# sch.net
KiCad netlist of a schematic drawn in Altium Designer
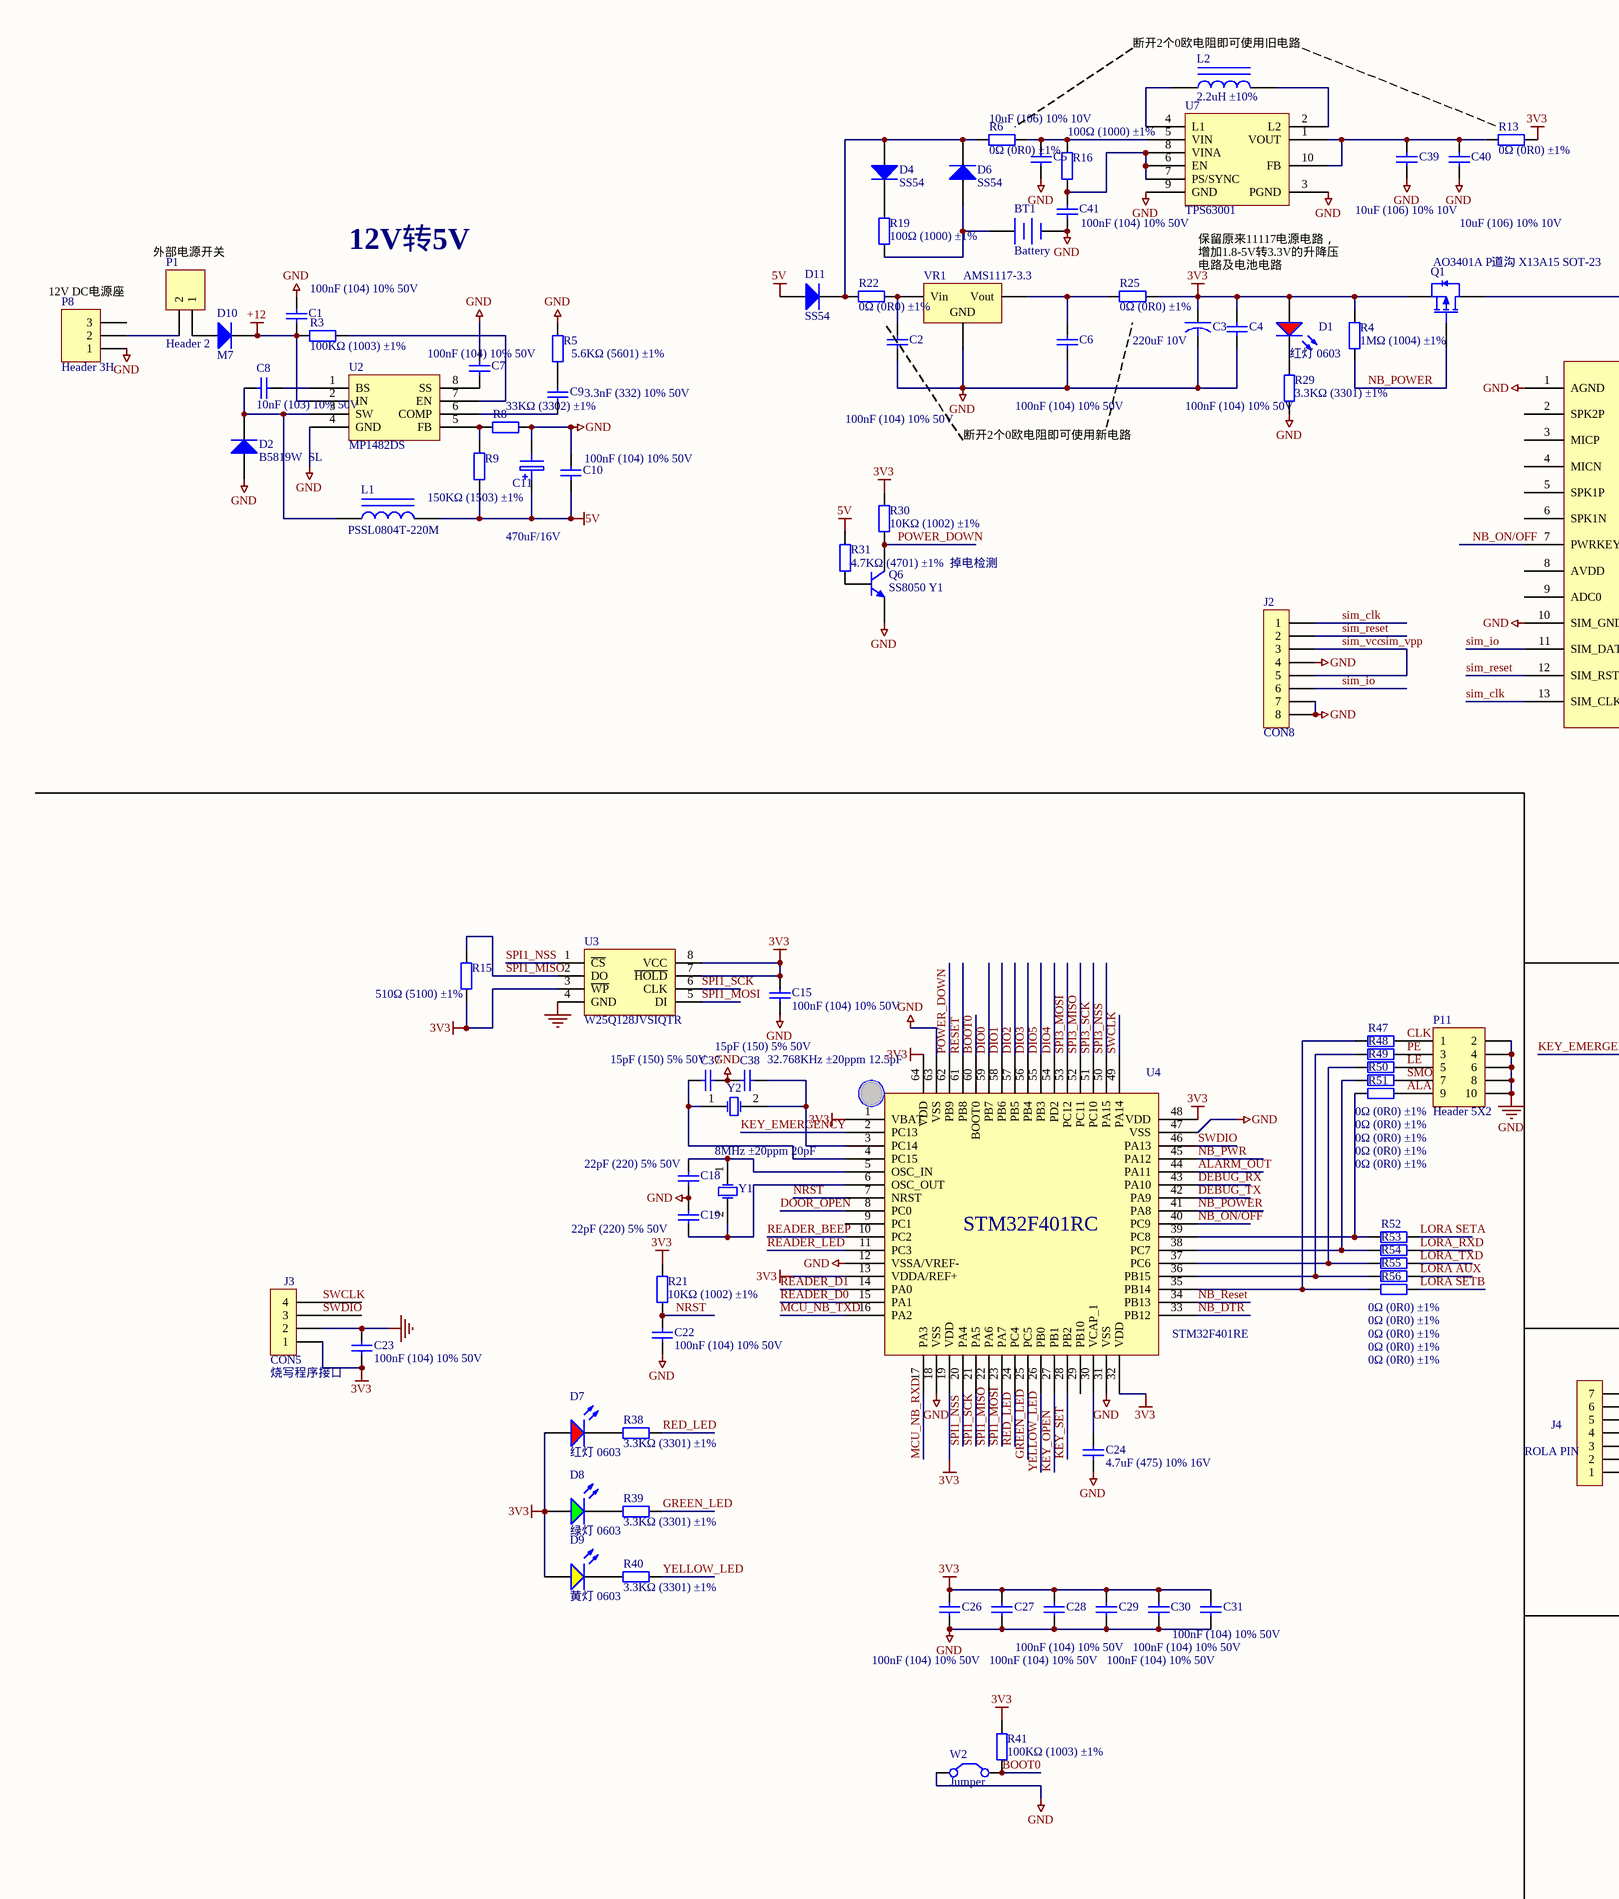
[diagram p0: sch.SchDoc, left]
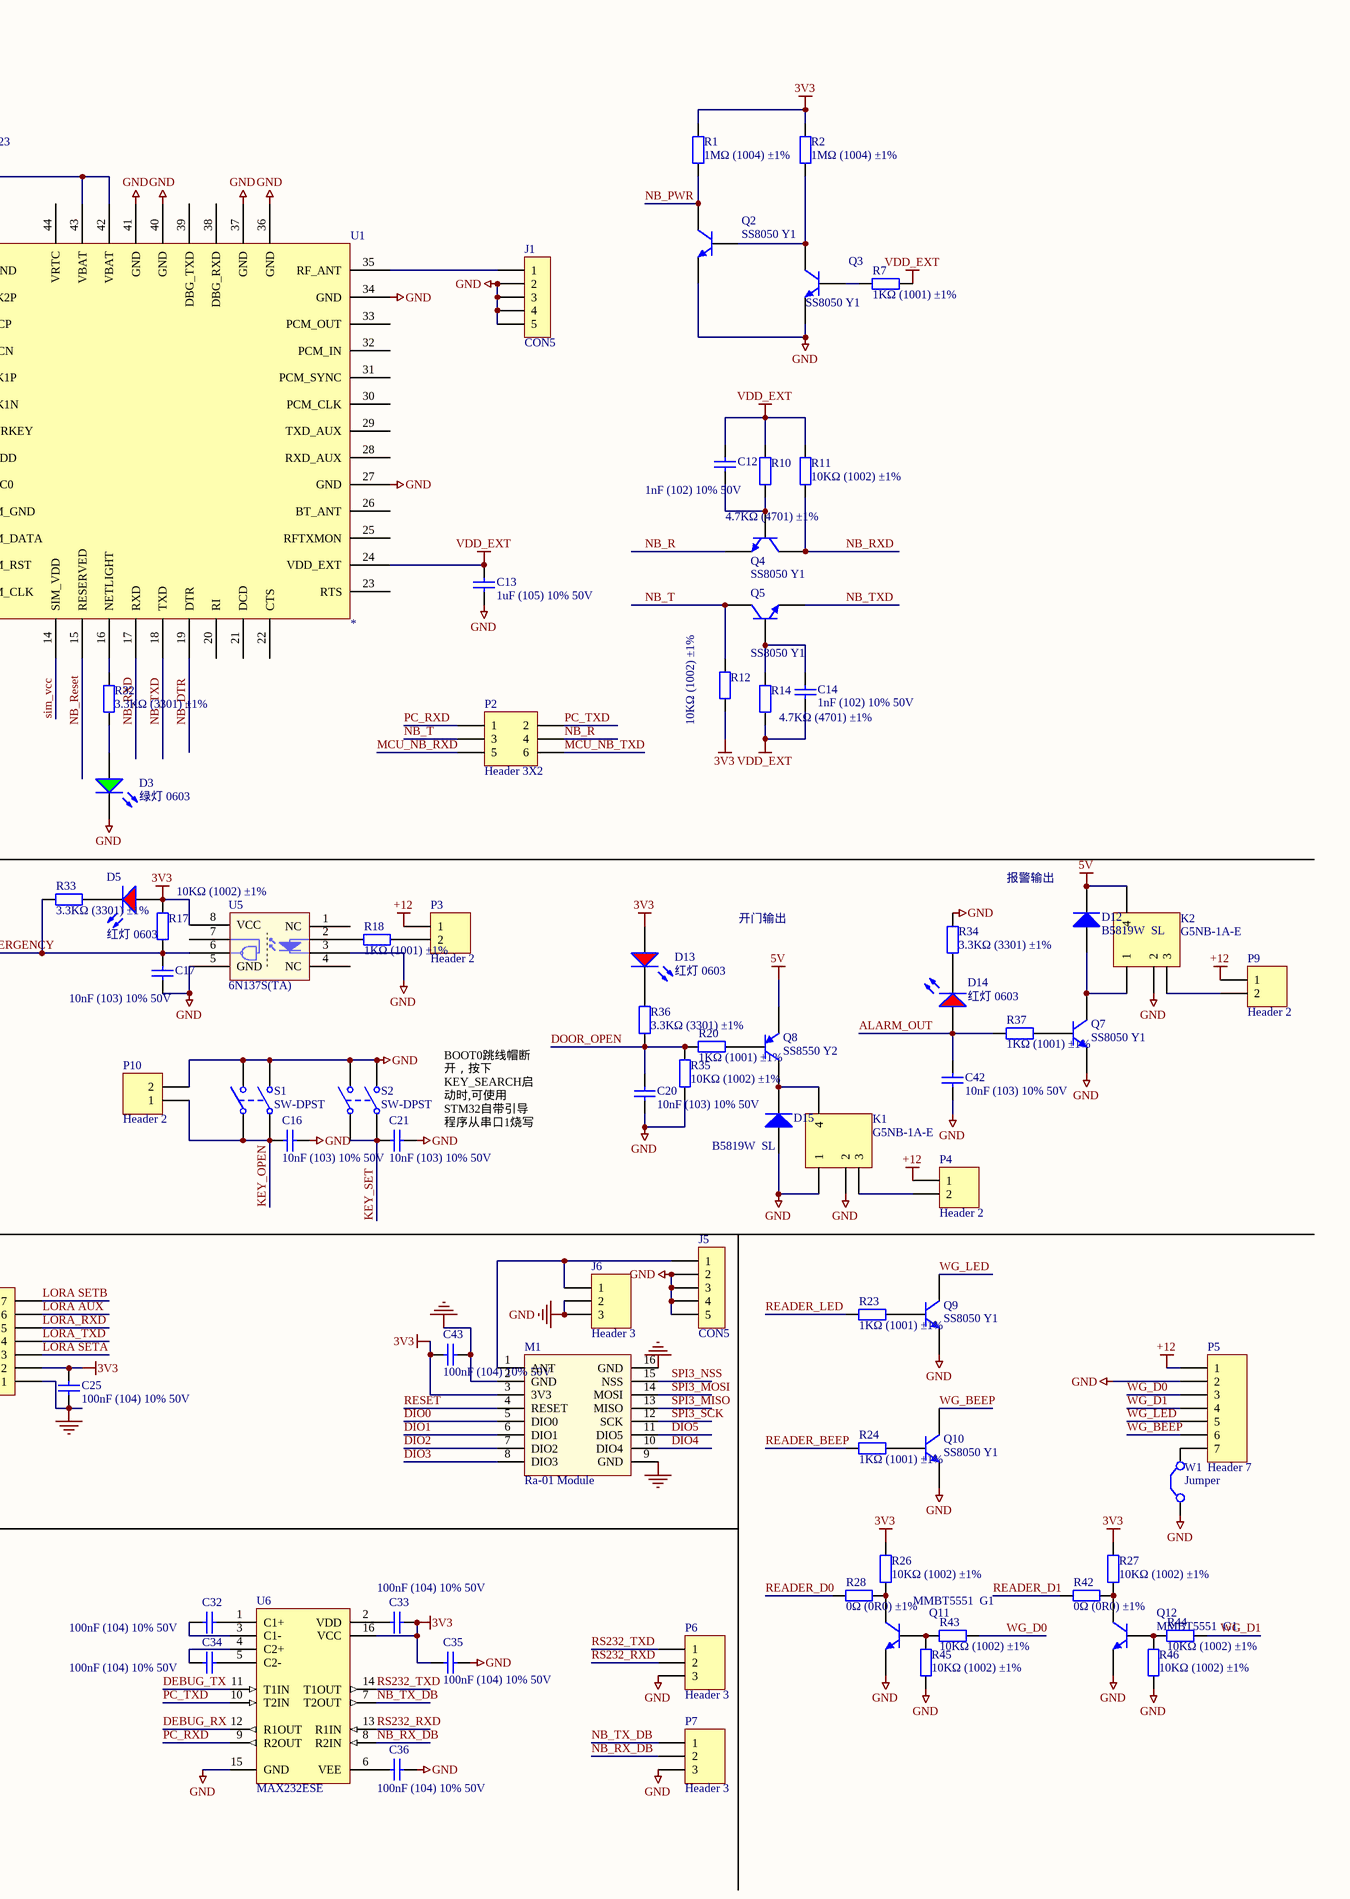
[diagram p1: sch.SchDoc, right]

(export (version "E")
  (design (tool "Eeschema 10.0.6"))
  (components
    (comp (ref "BT1")
      (value "Battery")
      (footprint "3V60R")
      (description "Multicell Battery")
      (fields (field (name "PUBLISHER") "Altium Limited"))
      (libsource (lib "Miscellaneous Devices") (part "Battery"))
    )
    (comp (ref "C1")
      (value "100nF (104) 10% 50V")
      (footprint "0603_C")
      (description "贴片电容")
      (libsource (lib "Cap") (part "0603 100nF (104) 10% 50V"))
    )
    (comp (ref "C2")
      (value "100nF (104) 10% 50V")
      (footprint "0603_C")
      (description "贴片电容")
      (libsource (lib "Cap") (part "0603 100nF (104) 10% 50V"))
    )
    (comp (ref "C3")
      (value "220uF 10V")
      (footprint "153CLV-0807")
      (description "Capacitor")
      (libsource (lib "*") (part "CAPACITOR"))
    )
    (comp (ref "C4")
      (value "100nF (104) 10% 50V")
      (footprint "0603_C")
      (description "贴片电容")
      (libsource (lib "Cap") (part "0603 100nF (104) 10% 50V"))
    )
    (comp (ref "C5")
      (value "10uF (106) 10% 10V")
      (footprint "0603_C")
      (description "贴片电容")
      (libsource (lib "Cap") (part "0603 10uF (106) 10% 10V"))
    )
    (comp (ref "C6")
      (value "100nF (104) 10% 50V")
      (footprint "0603_C")
      (description "贴片电容")
      (libsource (lib "Cap") (part "0603 100nF (104) 10% 50V"))
    )
    (comp (ref "C7")
      (value "100nF (104) 10% 50V")
      (footprint "0603_C")
      (description "贴片电容")
      (libsource (lib "Cap") (part "0603 100nF (104) 10% 50V"))
    )
    (comp (ref "C8")
      (value "10nF (103) 10% 50V")
      (footprint "0603_C")
      (description "贴片电容")
      (libsource (lib "Cap") (part "0603 10nF (103) 10% 50V"))
    )
    (comp (ref "C9")
      (value "3.3nF (332) 10% 50V")
      (footprint "0603_C")
      (description "贴片电容")
      (libsource (lib "Cap") (part "0603 3.3nF (332) 10% 50V"))
    )
    (comp (ref "C10")
      (value "100nF (104) 10% 50V")
      (footprint "0603_C")
      (description "贴片电容")
      (libsource (lib "Cap") (part "0603 100nF (104) 10% 50V"))
    )
    (comp (ref "C11")
      (value "470uF/16V")
      (footprint "153CLV-0810")
      (description "Electrolytic Capacitor")
      (libsource (lib "*") (part "ELECTRO1"))
    )
    (comp (ref "C12")
      (value "1nF (102) 10% 50V")
      (footprint "0603_C")
      (description "贴片电容")
      (libsource (lib "Cap") (part "0603 1nF (102) 10% 50V"))
    )
    (comp (ref "C13")
      (value "1uF (105) 10% 50V")
      (footprint "0603_C")
      (description "贴片电容")
      (libsource (lib "Cap") (part "0603 1uF (105) 10% 50V"))
    )
    (comp (ref "C14")
      (value "1nF (102) 10% 50V")
      (footprint "0603_C")
      (description "贴片电容")
      (libsource (lib "Cap") (part "0603 1nF (102) 10% 50V"))
    )
    (comp (ref "C15")
      (value "100nF (104) 10% 50V")
      (footprint "0603_C")
      (description "贴片电容")
      (libsource (lib "Cap") (part "0603 100nF (104) 10% 50V"))
    )
    (comp (ref "C16")
      (value "10nF (103) 10% 50V")
      (footprint "0603_C")
      (description "贴片电容")
      (libsource (lib "Cap") (part "0603 10nF (103) 10% 50V"))
    )
    (comp (ref "C17")
      (value "10nF (103) 10% 50V")
      (footprint "0603_C")
      (description "贴片电容")
      (libsource (lib "Cap") (part "0603 10nF (103) 10% 50V"))
    )
    (comp (ref "C18")
      (value "22pF (220) 5% 50V")
      (footprint "0603_C")
      (description "贴片电容")
      (libsource (lib "Cap") (part "0603 22pF (220) 5% 50V"))
    )
    (comp (ref "C19")
      (value "22pF (220) 5% 50V")
      (footprint "0603_C")
      (description "贴片电容")
      (libsource (lib "Cap") (part "0603 22pF (220) 5% 50V"))
    )
    (comp (ref "C20")
      (value "10nF (103) 10% 50V")
      (footprint "0603_C")
      (description "贴片电容")
      (libsource (lib "Cap") (part "0603 10nF (103) 10% 50V"))
    )
    (comp (ref "C21")
      (value "10nF (103) 10% 50V")
      (footprint "0603_C")
      (description "贴片电容")
      (libsource (lib "Cap") (part "0603 10nF (103) 10% 50V"))
    )
    (comp (ref "C22")
      (value "100nF (104) 10% 50V")
      (footprint "0603_C")
      (description "贴片电容")
      (libsource (lib "Cap") (part "0603 100nF (104) 10% 50V"))
    )
    (comp (ref "C23")
      (value "100nF (104) 10% 50V")
      (footprint "0603_C")
      (description "贴片电容")
      (libsource (lib "Cap") (part "0603 100nF (104) 10% 50V"))
    )
    (comp (ref "C24")
      (value "4.7uF (475) 10% 16V")
      (footprint "0603_C")
      (description "贴片电容")
      (libsource (lib "Cap") (part "0603 4.7uF (475) 10% 16V"))
    )
    (comp (ref "C25")
      (value "100nF (104) 10% 50V")
      (footprint "0603_C")
      (description "贴片电容")
      (libsource (lib "Cap") (part "0603 100nF (104) 10% 50V"))
    )
    (comp (ref "C26")
      (value "100nF (104) 10% 50V")
      (footprint "0603_C")
      (description "贴片电容")
      (libsource (lib "Cap") (part "0603 100nF (104) 10% 50V"))
    )
    (comp (ref "C27")
      (value "100nF (104) 10% 50V")
      (footprint "0603_C")
      (description "贴片电容")
      (libsource (lib "Cap") (part "0603 100nF (104) 10% 50V"))
    )
    (comp (ref "C28")
      (value "100nF (104) 10% 50V")
      (footprint "0603_C")
      (description "贴片电容")
      (libsource (lib "Cap") (part "0603 100nF (104) 10% 50V"))
    )
    (comp (ref "C29")
      (value "100nF (104) 10% 50V")
      (footprint "0603_C")
      (description "贴片电容")
      (libsource (lib "Cap") (part "0603 100nF (104) 10% 50V"))
    )
    (comp (ref "C30")
      (value "100nF (104) 10% 50V")
      (footprint "0603_C")
      (description "贴片电容")
      (libsource (lib "Cap") (part "0603 100nF (104) 10% 50V"))
    )
    (comp (ref "C31")
      (value "100nF (104) 10% 50V")
      (footprint "0603_C")
      (description "贴片电容")
      (libsource (lib "Cap") (part "0603 100nF (104) 10% 50V"))
    )
    (comp (ref "C32")
      (value "100nF (104) 10% 50V")
      (footprint "0603_C")
      (description "贴片电容")
      (libsource (lib "Cap") (part "0603 100nF (104) 10% 50V"))
    )
    (comp (ref "C33")
      (value "100nF (104) 10% 50V")
      (footprint "0603_C")
      (description "贴片电容")
      (libsource (lib "Cap") (part "0603 100nF (104) 10% 50V"))
    )
    (comp (ref "C34")
      (value "100nF (104) 10% 50V")
      (footprint "0603_C")
      (description "贴片电容")
      (libsource (lib "Cap") (part "0603 100nF (104) 10% 50V"))
    )
    (comp (ref "C35")
      (value "100nF (104) 10% 50V")
      (footprint "0603_C")
      (description "贴片电容")
      (libsource (lib "Cap") (part "0603 100nF (104) 10% 50V"))
    )
    (comp (ref "C36")
      (value "100nF (104) 10% 50V")
      (footprint "0603_C")
      (description "贴片电容")
      (libsource (lib "Cap") (part "0603 100nF (104) 10% 50V"))
    )
    (comp (ref "C37")
      (value "15pF (150) 5% 50V")
      (footprint "0603_C")
      (description "贴片电容")
      (libsource (lib "Cap") (part "0603 15pF (150) 5% 50V"))
    )
    (comp (ref "C38")
      (value "15pF (150) 5% 50V")
      (footprint "0603_C")
      (description "贴片电容")
      (libsource (lib "Cap") (part "0603 15pF (150) 5% 50V"))
    )
    (comp (ref "C39")
      (value "10uF (106) 10% 10V")
      (footprint "0603_C")
      (description "贴片电容")
      (libsource (lib "Cap") (part "0603 10uF (106) 10% 10V"))
    )
    (comp (ref "C40")
      (value "10uF (106) 10% 10V")
      (footprint "0603_C")
      (description "贴片电容")
      (libsource (lib "Cap") (part "0603 10uF (106) 10% 10V"))
    )
    (comp (ref "C41")
      (value "100nF (104) 10% 50V")
      (footprint "0603_C")
      (description "贴片电容")
      (libsource (lib "Cap") (part "0603 100nF (104) 10% 50V"))
    )
    (comp (ref "C42")
      (value "10nF (103) 10% 50V")
      (footprint "0603_C")
      (description "贴片电容")
      (libsource (lib "Cap") (part "0603 10nF (103) 10% 50V"))
    )
    (comp (ref "C43")
      (value "100nF (104) 10% 50V")
      (footprint "0603_C")
      (description "贴片电容")
      (libsource (lib "Cap") (part "0603 100nF (104) 10% 50V"))
    )
    (comp (ref "D1")
      (value "红灯 0603")
      (footprint "0603_LED_S1")
      (description "发光二极管")
      (libsource (lib "LED") (part "0603 红灯"))
    )
    (comp (ref "D2")
      (value "B5819W  SL")
      (footprint "SOD-123")
      (description "肖特基二极管")
      (libsource (lib "Diode") (part "SOD-123 B5819W  SL"))
    )
    (comp (ref "D3")
      (value "绿灯 0603")
      (footprint "0603_LED_S1")
      (description "发光二极管")
      (libsource (lib "LED") (part "0603 绿灯"))
    )
    (comp (ref "D4")
      (value "SS54")
      (footprint "SMA(DO-214AC)_S1")
      (description "二极管")
      (libsource (lib "Diode") (part "SMA(DO-214AC) SS54"))
    )
    (comp (ref "D5")
      (value "红灯 0603")
      (footprint "0603_LED_S1")
      (description "发光二极管")
      (libsource (lib "LED") (part "0603 红灯"))
    )
    (comp (ref "D6")
      (value "SS54")
      (footprint "SMA(DO-214AC)_S1")
      (description "二极管")
      (libsource (lib "Diode") (part "SMA(DO-214AC) SS54"))
    )
    (comp (ref "D7")
      (value "红灯 0603")
      (footprint "0603_LED_S1")
      (description "发光二极管")
      (libsource (lib "LED") (part "0603 红灯"))
    )
    (comp (ref "D8")
      (value "绿灯 0603")
      (footprint "0603_LED_S1")
      (description "发光二极管")
      (libsource (lib "LED") (part "0603 绿灯"))
    )
    (comp (ref "D9")
      (value "黄灯 0603")
      (footprint "0603_LED_S1")
      (description "发光二极管")
      (libsource (lib "LED") (part "0603 黄灯"))
    )
    (comp (ref "D10")
      (value "M7")
      (footprint "SMA(DO-214AC)_S1")
      (description "二极管")
      (libsource (lib "Diode") (part "SMA(DO-214AC) M7"))
    )
    (comp (ref "D11")
      (value "SS54")
      (footprint "SMA(DO-214AC)_S1")
      (description "二极管")
      (libsource (lib "Diode") (part "SMA(DO-214AC) SS54"))
    )
    (comp (ref "D12")
      (value "B5819W  SL")
      (footprint "SOD-123")
      (description "肖特基二极管")
      (libsource (lib "Diode") (part "SOD-123 B5819W  SL"))
    )
    (comp (ref "D13")
      (value "红灯 0603")
      (footprint "0603_LED_S1")
      (description "发光二极管")
      (libsource (lib "LED") (part "0603 红灯"))
    )
    (comp (ref "D14")
      (value "红灯 0603")
      (footprint "0603_LED_S1")
      (description "发光二极管")
      (libsource (lib "LED") (part "0603 红灯"))
    )
    (comp (ref "D15")
      (value "B5819W  SL")
      (footprint "SOD-123")
      (description "肖特基二极管")
      (libsource (lib "Diode") (part "SOD-123 B5819W  SL"))
    )
    (comp (ref "J1")
      (value "CON5")
      (footprint "T-5P")
      (description "Connector")
      (libsource (lib "*") (part "CON5"))
    )
    (comp (ref "J2")
      (value "CON8")
      (footprint "NANOSIM")
      (description "Connector")
      (libsource (lib "*") (part "CON8"))
    )
    (comp (ref "J3")
      (value "CON5")
      (footprint "SIP4")
      (description "Connector")
      (libsource (lib "*") (part "CON4"))
    )
    (comp (ref "J4")
      (value "ROLA PIN")
      (footprint "ROLA MODULE")
      (description "Connector")
      (libsource (lib "*") (part "CON7"))
    )
    (comp (ref "J5")
      (value "CON5")
      (footprint "T-5P")
      (description "Connector")
      (libsource (lib "*") (part "CON5"))
    )
    (comp (ref "J6")
      (value "Header 3")
      (footprint "COAXIAL/SMD/CON/V/I-PEX/W08-5801")
      (description "Header, 3-Pin")
      (fields (field (name "PUBLISHER") "Altium Limited"))
      (libsource (lib "Miscellaneous Connectors") (part "Header 3"))
    )
    (comp (ref "K1") (value "G5NB-1A-E") (footprint "G5NB-1A") (libsource (lib "*") (part "G5NB-1A-E")))
    (comp (ref "K2") (value "G5NB-1A-E") (footprint "G5NB-1A") (libsource (lib "*") (part "G5NB-1A-E")))
    (comp (ref "L1") (value "PSSL0804T-220M") (footprint "L7-8") (libsource (lib "*") (part "INDUCTOR IRON")))
    (comp (ref "L2")
      (value "2.2uH ±10%")
      (footprint "L4532M")
      (description "贴片电感")
      (libsource (lib "IUD") (part "0805 2.2uH 10%"))
    )
    (comp (ref "M1")
      (value "Ra-01 Module")
      (footprint "Ra-01 Module")
      (libsource (lib "Ra-02 Module") (part "Ra-01 Module"))
    )
    (comp (ref "P1")
      (value "Header 2")
      (footprint "MSTBV2")
      (description "Header, 2-Pin")
      (fields (field (name "PUBLISHER") "Altium Limited"))
      (libsource (lib "Miscellaneous Connectors") (part "Header 2"))
    )
    (comp (ref "P2")
      (value "Header 3X2")
      (footprint "HDR2X3")
      (description "Header, 3-Pin, Dual row")
      (fields (field (name "PUBLISHER") "Altium Limited"))
      (libsource (lib "Miscellaneous Connectors") (part "Header 3X2"))
    )
    (comp (ref "P3")
      (value "Header 2")
      (footprint "MSTBV2")
      (description "Header, 2-Pin")
      (fields (field (name "PUBLISHER") "Altium Limited"))
      (libsource (lib "Miscellaneous Connectors") (part "Header 2"))
    )
    (comp (ref "P4")
      (value "Header 2")
      (footprint "MSTBV2")
      (description "Header, 2-Pin")
      (fields (field (name "PUBLISHER") "Altium Limited"))
      (libsource (lib "Miscellaneous Connectors") (part "Header 2"))
    )
    (comp (ref "P5")
      (value "Header 7")
      (footprint "MSTBV7")
      (description "Header, 7-Pin")
      (fields (field (name "PUBLISHER") "Altium Limited"))
      (libsource (lib "Miscellaneous Connectors") (part "Header 7"))
    )
    (comp (ref "P6")
      (value "Header 3")
      (footprint "HDR1X3")
      (description "Header, 3-Pin")
      (fields (field (name "PUBLISHER") "Altium Limited"))
      (libsource (lib "Miscellaneous Connectors") (part "Header 3"))
    )
    (comp (ref "P7")
      (value "Header 3")
      (footprint "HDR1X3")
      (description "Header, 3-Pin")
      (fields (field (name "PUBLISHER") "Altium Limited"))
      (libsource (lib "Miscellaneous Connectors") (part "Header 3"))
    )
    (comp (ref "P8")
      (value "Header 3H")
      (footprint "POWER_SOCK _INSERT_5")
      (description "Header, 3-Pin, Right Angle")
      (fields (field (name "PUBLISHER") "Altium Limited"))
      (libsource (lib "Miscellaneous Connectors") (part "Header 3H"))
    )
    (comp (ref "P9")
      (value "Header 2")
      (footprint "MSTBV2")
      (description "Header, 2-Pin")
      (fields (field (name "PUBLISHER") "Altium Limited"))
      (libsource (lib "Miscellaneous Connectors") (part "Header 2"))
    )
    (comp (ref "P10")
      (value "Header 2")
      (footprint "MSTBV2")
      (description "Header, 2-Pin")
      (fields (field (name "PUBLISHER") "Altium Limited"))
      (libsource (lib "") (part "Header 2_1"))
    )
    (comp (ref "P11")
      (value "Header 5X2")
      (footprint "ML10")
      (description "Header, 5-Pin, Dual row")
      (fields (field (name "PUBLISHER") "Altium Limited"))
      (libsource (lib "Miscellaneous Connectors") (part "Header 5X2"))
    )
    (comp (ref "Q1")
      (value "AO3401A P道沟 X13A15 SOT-23")
      (footprint "SOT-23-3L")
      (description "MOS(场效应管)")
      (libsource (lib "MOS") (part "AO3401A P道沟 X13A15 SOT-23"))
    )
    (comp (ref "Q2")
      (value "SS8050 Y1")
      (footprint "SOT-23(SOT-23-3)")
      (description "三极管")
      (libsource (lib "Transistor_NPN") (part "SOT-23 SS8050 Y1"))
    )
    (comp (ref "Q3")
      (value "SS8050 Y1")
      (footprint "SOT-23(SOT-23-3)")
      (description "三极管")
      (libsource (lib "Transistor_NPN") (part "SOT-23 SS8050 Y1"))
    )
    (comp (ref "Q4")
      (value "SS8050 Y1")
      (footprint "SOT-23(SOT-23-3)")
      (description "三极管")
      (libsource (lib "Transistor_NPN") (part "SOT-23 SS8050 Y1"))
    )
    (comp (ref "Q5")
      (value "SS8050 Y1")
      (footprint "SOT-23(SOT-23-3)")
      (description "三极管")
      (libsource (lib "Transistor_NPN") (part "SOT-23 SS8050 Y1"))
    )
    (comp (ref "Q6")
      (value "SS8050 Y1")
      (footprint "SOT-23(SOT-23-3)")
      (description "三极管")
      (libsource (lib "Transistor_NPN") (part "SOT-23 SS8050 Y1"))
    )
    (comp (ref "Q7")
      (value "SS8050 Y1")
      (footprint "SOT-23(SOT-23-3)")
      (description "三极管")
      (libsource (lib "Transistor_NPN") (part "SOT-23 SS8050 Y1"))
    )
    (comp (ref "Q8")
      (value "SS8550 Y2")
      (footprint "SOT-23(SOT-23-3)")
      (description "三极管")
      (libsource (lib "Transistor_PNP") (part "SOT-23 SS8550 Y2"))
    )
    (comp (ref "Q9")
      (value "SS8050 Y1")
      (footprint "SOT-23(SOT-23-3)")
      (description "三极管")
      (libsource (lib "Transistor_NPN") (part "SOT-23 SS8050 Y1"))
    )
    (comp (ref "Q10")
      (value "SS8050 Y1")
      (footprint "SOT-23(SOT-23-3)")
      (description "三极管")
      (libsource (lib "Transistor_NPN") (part "SOT-23 SS8050 Y1"))
    )
    (comp (ref "Q11")
      (value "MMBT5551  G1")
      (footprint "SOT-23(SOT-23-3)")
      (description "三极管")
      (libsource (lib "Transistor_NPN") (part "SOT-23 MMBT5551  G1"))
    )
    (comp (ref "Q12")
      (value "MMBT5551  G1")
      (footprint "SOT-23(SOT-23-3)")
      (description "三极管")
      (libsource (lib "Transistor_NPN") (part "SOT-23 MMBT5551  G1"))
    )
    (comp (ref "R1")
      (value "1MΩ (1004) ±1%")
      (footprint "0603_R")
      (description "贴片电阻")
      (libsource (lib "RES") (part "0603 1MΩ (1004) 1%"))
    )
    (comp (ref "R2")
      (value "1MΩ (1004) ±1%")
      (footprint "0603_R")
      (description "贴片电阻")
      (libsource (lib "RES") (part "0603 1MΩ (1004) 1%"))
    )
    (comp (ref "R3")
      (value "100KΩ (1003) ±1%")
      (footprint "0603_R")
      (description "贴片电阻")
      (libsource (lib "RES") (part "0603 100KΩ (1003) 1%"))
    )
    (comp (ref "R4")
      (value "1MΩ (1004) ±1%")
      (footprint "0603_R")
      (description "贴片电阻")
      (libsource (lib "RES") (part "0603 1MΩ (1004) 1%"))
    )
    (comp (ref "R5")
      (value "5.6KΩ (5601) ±1%")
      (footprint "0603_R")
      (description "贴片电阻")
      (libsource (lib "RES") (part "0603 5.6KΩ (5601) 1%"))
    )
    (comp (ref "R6")
      (value "0Ω (0R0) ±1%")
      (footprint "0603_R")
      (description "贴片电阻")
      (libsource (lib "RES") (part "0603 0Ω (0R0) 1%"))
    )
    (comp (ref "R7")
      (value "1KΩ (1001) ±1%")
      (footprint "0603_R")
      (description "贴片电阻")
      (libsource (lib "RES") (part "0603 1KΩ (1001) 1%"))
    )
    (comp (ref "R8")
      (value "33KΩ (3302) ±1%")
      (footprint "0603_R")
      (description "贴片电阻")
      (libsource (lib "RES") (part "0603 33KΩ (3302) 1%"))
    )
    (comp (ref "R9")
      (value "150KΩ (1503) ±1%")
      (footprint "0603_R")
      (description "贴片电阻")
      (libsource (lib "RES") (part "0603 150KΩ (1503) 1%"))
    )
    (comp (ref "R10")
      (value "4.7KΩ (4701) ±1%")
      (footprint "0603_R")
      (description "贴片电阻")
      (libsource (lib "RES") (part "0603 4.7KΩ (4701) 1%"))
    )
    (comp (ref "R11")
      (value "10KΩ (1002) ±1%")
      (footprint "0603_R")
      (description "贴片电阻")
      (libsource (lib "") (part "0603 10KΩ (1002) 1%_1"))
    )
    (comp (ref "R12")
      (value "10KΩ (1002) ±1%")
      (footprint "0603_R")
      (description "贴片电阻")
      (libsource (lib "") (part "0603 10KΩ (1002) 1%_1"))
    )
    (comp (ref "R13")
      (value "0Ω (0R0) ±1%")
      (footprint "0603_R")
      (description "贴片电阻")
      (libsource (lib "RES") (part "0603 0Ω (0R0) 1%"))
    )
    (comp (ref "R14")
      (value "4.7KΩ (4701) ±1%")
      (footprint "0603_R")
      (description "贴片电阻")
      (libsource (lib "RES") (part "0603 4.7KΩ (4701) 1%"))
    )
    (comp (ref "R15")
      (value "510Ω (5100) ±1%")
      (footprint "0603_R")
      (description "贴片电阻")
      (libsource (lib "RES") (part "0603 510Ω (5100) 1%"))
    )
    (comp (ref "R16")
      (value "100Ω (1000) ±1%")
      (footprint "0603_R")
      (description "贴片电阻")
      (libsource (lib "RES") (part "0603 100Ω (1000) 1%"))
    )
    (comp (ref "R17")
      (value "10KΩ (1002) ±1%")
      (footprint "0603_R")
      (description "贴片电阻")
      (libsource (lib "RES") (part "0603 10KΩ (1002) 1%"))
    )
    (comp (ref "R18")
      (value "1KΩ (1001) ±1%")
      (footprint "1206_R")
      (description "贴片电阻")
      (libsource (lib "RES") (part "1206 1KΩ (1001) 1%"))
    )
    (comp (ref "R19")
      (value "100Ω (1000) ±1%")
      (footprint "0805_R")
      (description "贴片电阻")
      (libsource (lib "RES") (part "0805 100Ω (1000) 1%"))
    )
    (comp (ref "R20")
      (value "1KΩ (1001) ±1%")
      (footprint "0603_R")
      (description "贴片电阻")
      (libsource (lib "RES") (part "0603 1KΩ (1001) 1%"))
    )
    (comp (ref "R21")
      (value "10KΩ (1002) ±1%")
      (footprint "0603_R")
      (description "贴片电阻")
      (libsource (lib "") (part "0603 10KΩ (1002) 1%_1"))
    )
    (comp (ref "R22")
      (value "0Ω (0R0) ±1%")
      (footprint "0603_R")
      (description "贴片电阻")
      (libsource (lib "RES") (part "0603 0Ω (0R0) 1%"))
    )
    (comp (ref "R23")
      (value "1KΩ (1001) ±1%")
      (footprint "0603_R")
      (description "贴片电阻")
      (libsource (lib "RES") (part "0603 1KΩ (1001) 1%"))
    )
    (comp (ref "R24")
      (value "1KΩ (1001) ±1%")
      (footprint "0603_R")
      (description "贴片电阻")
      (libsource (lib "RES") (part "0603 1KΩ (1001) 1%"))
    )
    (comp (ref "R25")
      (value "0Ω (0R0) ±1%")
      (footprint "0603_R")
      (description "贴片电阻")
      (libsource (lib "RES") (part "0603 0Ω (0R0) 1%"))
    )
    (comp (ref "R26")
      (value "10KΩ (1002) ±1%")
      (footprint "0603_R")
      (description "贴片电阻")
      (libsource (lib "RES") (part "0603 10KΩ (1002) 1%"))
    )
    (comp (ref "R27")
      (value "10KΩ (1002) ±1%")
      (footprint "0603_R")
      (description "贴片电阻")
      (libsource (lib "RES") (part "0603 10KΩ (1002) 1%"))
    )
    (comp (ref "R28")
      (value "0Ω (0R0) ±1%")
      (footprint "0603_R")
      (description "贴片电阻")
      (libsource (lib "RES") (part "0603 0Ω (0R0) 1%"))
    )
    (comp (ref "R29")
      (value "3.3KΩ (3301) ±1%")
      (footprint "0603_R")
      (description "贴片电阻")
      (libsource (lib "RES") (part "0603 3.3KΩ (3301) 1%"))
    )
    (comp (ref "R30")
      (value "10KΩ (1002) ±1%")
      (footprint "0603_R")
      (description "贴片电阻")
      (libsource (lib "") (part "0603 10KΩ (1002) 1%_1"))
    )
    (comp (ref "R31")
      (value "4.7KΩ (4701) ±1%")
      (footprint "0603_R")
      (description "贴片电阻")
      (libsource (lib "RES") (part "0603 4.7KΩ (4701) 1%"))
    )
    (comp (ref "R32")
      (value "3.3KΩ (3301) ±1%")
      (footprint "0603_R")
      (description "贴片电阻")
      (libsource (lib "RES") (part "0603 3.3KΩ (3301) 1%"))
    )
    (comp (ref "R33")
      (value "3.3KΩ (3301) ±1%")
      (footprint "0603_R")
      (description "贴片电阻")
      (libsource (lib "") (part "0603 3.3KΩ (3301) 1%_1"))
    )
    (comp (ref "R34")
      (value "3.3KΩ (3301) ±1%")
      (footprint "0603_R")
      (description "贴片电阻")
      (libsource (lib "RES") (part "0603 3.3KΩ (3301) 1%"))
    )
    (comp (ref "R35")
      (value "10KΩ (1002) ±1%")
      (footprint "0603_R")
      (description "贴片电阻")
      (libsource (lib "") (part "0603 10KΩ (1002) 1%_1"))
    )
    (comp (ref "R36")
      (value "3.3KΩ (3301) ±1%")
      (footprint "0603_R")
      (description "贴片电阻")
      (libsource (lib "") (part "0603 3.3KΩ (3301) 1%_2"))
    )
    (comp (ref "R37")
      (value "1KΩ (1001) ±1%")
      (footprint "0603_R")
      (description "贴片电阻")
      (libsource (lib "RES") (part "0603 1KΩ (1001) 1%"))
    )
    (comp (ref "R38")
      (value "3.3KΩ (3301) ±1%")
      (footprint "0603_R")
      (description "贴片电阻")
      (libsource (lib "") (part "0603 3.3KΩ (3301) 1%_1"))
    )
    (comp (ref "R39")
      (value "3.3KΩ (3301) ±1%")
      (footprint "0603_R")
      (description "贴片电阻")
      (libsource (lib "") (part "0603 3.3KΩ (3301) 1%_1"))
    )
    (comp (ref "R40")
      (value "3.3KΩ (3301) ±1%")
      (footprint "0603_R")
      (description "贴片电阻")
      (libsource (lib "") (part "0603 3.3KΩ (3301) 1%_1"))
    )
    (comp (ref "R41")
      (value "100KΩ (1003) ±1%")
      (footprint "0603_R")
      (description "贴片电阻")
      (libsource (lib "") (part "0603 100KΩ (1003) 1%_1"))
    )
    (comp (ref "R42")
      (value "0Ω (0R0) ±1%")
      (footprint "0603_R")
      (description "贴片电阻")
      (libsource (lib "RES") (part "0603 0Ω (0R0) 1%"))
    )
    (comp (ref "R43")
      (value "10KΩ (1002) ±1%")
      (footprint "0603_R")
      (description "贴片电阻")
      (libsource (lib "") (part "0603 10KΩ (1002) 1%_2"))
    )
    (comp (ref "R44")
      (value "10KΩ (1002) ±1%")
      (footprint "0603_R")
      (description "贴片电阻")
      (libsource (lib "") (part "0603 10KΩ (1002) 1%_2"))
    )
    (comp (ref "R45")
      (value "10KΩ (1002) ±1%")
      (footprint "0603_R")
      (description "贴片电阻")
      (libsource (lib "RES") (part "0603 10KΩ (1002) 1%"))
    )
    (comp (ref "R46")
      (value "10KΩ (1002) ±1%")
      (footprint "0603_R")
      (description "贴片电阻")
      (libsource (lib "RES") (part "0603 10KΩ (1002) 1%"))
    )
    (comp (ref "R47")
      (value "0Ω (0R0) ±1%")
      (footprint "0603_R")
      (description "贴片电阻")
      (libsource (lib "RES") (part "0603 0Ω (0R0) 1%"))
    )
    (comp (ref "R48")
      (value "0Ω (0R0) ±1%")
      (footprint "0603_R")
      (description "贴片电阻")
      (libsource (lib "RES") (part "0603 0Ω (0R0) 1%"))
    )
    (comp (ref "R49")
      (value "0Ω (0R0) ±1%")
      (footprint "0603_R")
      (description "贴片电阻")
      (libsource (lib "RES") (part "0603 0Ω (0R0) 1%"))
    )
    (comp (ref "R50")
      (value "0Ω (0R0) ±1%")
      (footprint "0603_R")
      (description "贴片电阻")
      (libsource (lib "RES") (part "0603 0Ω (0R0) 1%"))
    )
    (comp (ref "R51")
      (value "0Ω (0R0) ±1%")
      (footprint "0603_R")
      (description "贴片电阻")
      (libsource (lib "RES") (part "0603 0Ω (0R0) 1%"))
    )
    (comp (ref "R52")
      (value "0Ω (0R0) ±1%")
      (footprint "0603_R")
      (description "贴片电阻")
      (libsource (lib "RES") (part "0603 0Ω (0R0) 1%"))
    )
    (comp (ref "R53")
      (value "0Ω (0R0) ±1%")
      (footprint "0603_R")
      (description "贴片电阻")
      (libsource (lib "RES") (part "0603 0Ω (0R0) 1%"))
    )
    (comp (ref "R54")
      (value "0Ω (0R0) ±1%")
      (footprint "0603_R")
      (description "贴片电阻")
      (libsource (lib "RES") (part "0603 0Ω (0R0) 1%"))
    )
    (comp (ref "R55")
      (value "0Ω (0R0) ±1%")
      (footprint "0603_R")
      (description "贴片电阻")
      (libsource (lib "RES") (part "0603 0Ω (0R0) 1%"))
    )
    (comp (ref "R56")
      (value "0Ω (0R0) ±1%")
      (footprint "0603_R")
      (description "贴片电阻")
      (libsource (lib "RES") (part "0603 0Ω (0R0) 1%"))
    )
    (comp (ref "S1")
      (value "SW-DPST")
      (footprint "12*12_key")
      (description "Double-Pole, Single-Throw Switch")
      (fields (field (name "PUBLISHER") "Altium Limited"))
      (libsource (lib "Miscellaneous Devices") (part "SW-DPST"))
    )
    (comp (ref "S2")
      (value "SW-DPST")
      (footprint "12*12_key")
      (description "Double-Pole, Single-Throw Switch")
      (fields (field (name "PUBLISHER") "Altium Limited"))
      (libsource (lib "Miscellaneous Devices") (part "SW-DPST"))
    )
    (comp (ref "U1") (value "*") (footprint "M26") (libsource (lib "*") (part "M26")))
    (comp (ref "U2")
      (value "MP1482DS")
      (footprint "SOIC-8_150mil")
      (description "电源芯片")
      (libsource (lib "IC") (part "MP1482DS_[C14867]"))
    )
    (comp (ref "U3")
      (value "W25Q128JVSIQTR")
      (footprint "SOIC-8_208mil")
      (description "Flash ROM")
      (libsource (lib "IC") (part "W25Q128JVSIQTR_[C97521]"))
    )
    (comp (ref "U4") (value "STM32F401RE") (footprint "LQFP64") (libsource (lib "*") (part "STM32F401RC")))
    (comp (ref "U5")
      (value "6N137S(TA)")
      (footprint "SMD-8_6.3mm")
      (description "贴片光耦")
      (libsource (lib "IC") (part "6N137S(TA)_[C16496]"))
    )
    (comp (ref "U6")
      (value "MAX232ESE")
      (footprint "SOIC-16_150mil")
      (description "RS232")
      (libsource (lib "IC") (part "MAX232ESE_[C26860]"))
    )
    (comp (ref "U7")
      (value "TPS63001")
      (footprint "DRC-S-PVSON-N10")
      (libsource (lib "Schlib1") (part "TPS63001"))
    )
    (comp (ref "VR1")
      (value "AMS1117-3.3")
      (footprint "SOT-223")
      (description "低压差线性稳压(LDO)")
      (libsource (lib "LDO") (part "SOT-223 AMS1117-3.3"))
    )
    (comp (ref "W1")
      (value "Jumper")
      (footprint "JP1")
      (description "Jumper Wire")
      (fields (field (name "PUBLISHER") "Altium Limited"))
      (libsource (lib "Miscellaneous Devices") (part "Jumper"))
    )
    (comp (ref "W2")
      (value "Jumper")
      (footprint "JP1")
      (description "Jumper Wire")
      (fields (field (name "PUBLISHER") "Altium Limited"))
      (libsource (lib "Miscellaneous Devices") (part "Jumper"))
    )
    (comp (ref "Y1")
      (value "8MHz ±20ppm 20pF")
      (footprint "SMD-5032_2P")
      (description "贴片晶振")
      (libsource (lib "CrystalOscillator") (part "SMD-5032_2P 8MHz 20ppm 20pF"))
    )
    (comp (ref "Y2")
      (value "32.768KHz ±20ppm 12.5pF")
      (footprint "SMD-3215_2P FC - 135")
      (description "贴片晶振")
      (libsource (lib "CrystalOscillator") (part "SMD-3215_2P 32.768KHz 20ppm 12.5pF"))
    )
  )
  (nets
    (net (code "1") (name "+12") (class "Default")
      (node (ref "C1") (pin "2") (pinfunction "2_2") (pintype "passive"))
      (node (ref "D10") (pin "2") (pinfunction "K_2") (pintype "passive"))
      (node (ref "P3") (pin "1") (pinfunction "1_1") (pintype "passive"))
      (node (ref "P4") (pin "1") (pinfunction "1_1") (pintype "passive"))
      (node (ref "P5") (pin "1") (pinfunction "1_1") (pintype "passive"))
      (node (ref "P9") (pin "1") (pinfunction "1_1") (pintype "passive"))
      (node (ref "R3") (pin "1") (pinfunction "1_1") (pintype "passive"))
      (node (ref "U2") (pin "2") (pinfunction "IN_2") (pintype "passive"))
    )
    (net (code "3") (name "/ALARM") (class "Default")
      (node (ref "P11") (pin "9") (pinfunction "9_9") (pintype "passive"))
      (node (ref "R51") (pin "2") (pinfunction "2_2") (pintype "passive"))
    )
    (net (code "4") (name "/ALARM_OUT") (class "Default")
      (node (ref "C42") (pin "1") (pinfunction "1_1") (pintype "passive"))
      (node (ref "D14") (pin "A") (pinfunction "A_A") (pintype "passive"))
      (node (ref "R37") (pin "1") (pinfunction "1_1") (pintype "passive"))
      (node (ref "U4") (pin "44") (pinfunction "PA11_44") (pintype "passive"))
    )
    (net (code "5") (name "/BOOT0") (class "Default")
      (node (ref "R41") (pin "1") (pinfunction "1_1") (pintype "passive"))
      (node (ref "U4") (pin "60") (pinfunction "BOOT0_60") (pintype "passive"))
      (node (ref "W2") (pin "2") (pinfunction "C2_2") (pintype "passive"))
    )
    (net (code "6") (name "/CLK") (class "Default")
      (node (ref "P11") (pin "1") (pinfunction "1_1") (pintype "passive"))
      (node (ref "R47") (pin "2") (pinfunction "2_2") (pintype "passive"))
    )
    (net (code "7") (name "/DEBUG_RX") (class "Default")
      (node (ref "U4") (pin "43") (pinfunction "PA10_43") (pintype "passive"))
      (node (ref "U6") (pin "12") (pinfunction "R1OUT_12") (pintype "output"))
    )
    (net (code "8") (name "/DEBUG_TX") (class "Default")
      (node (ref "U4") (pin "42") (pinfunction "PA9_42") (pintype "passive"))
      (node (ref "U6") (pin "11") (pinfunction "T1IN_11") (pintype "input"))
    )
    (net (code "9") (name "/DIO0") (class "Default")
      (node (ref "M1") (pin "5") (pinfunction "DIO0_5") (pintype "passive"))
      (node (ref "U4") (pin "59") (pinfunction "PB7_59") (pintype "passive"))
    )
    (net (code "10") (name "/DIO1") (class "Default")
      (node (ref "M1") (pin "6") (pinfunction "DIO1_6") (pintype "passive"))
      (node (ref "U4") (pin "58") (pinfunction "PB6_58") (pintype "passive"))
    )
    (net (code "11") (name "/DIO2") (class "Default")
      (node (ref "M1") (pin "7") (pinfunction "DIO2_7") (pintype "passive"))
      (node (ref "U4") (pin "57") (pinfunction "PB5_57") (pintype "passive"))
    )
    (net (code "12") (name "/DIO3") (class "Default")
      (node (ref "M1") (pin "8") (pinfunction "DIO3_8") (pintype "passive"))
      (node (ref "U4") (pin "56") (pinfunction "PB4_56") (pintype "passive"))
    )
    (net (code "13") (name "/DIO4") (class "Default")
      (node (ref "M1") (pin "10") (pinfunction "DIO4_10") (pintype "passive"))
      (node (ref "U4") (pin "54") (pinfunction "PD2_54") (pintype "passive"))
    )
    (net (code "14") (name "/DIO5") (class "Default")
      (node (ref "M1") (pin "11") (pinfunction "DIO5_11") (pintype "passive"))
      (node (ref "U4") (pin "55") (pinfunction "PB3_55") (pintype "passive"))
    )
    (net (code "15") (name "/DOOR_OPEN") (class "Default")
      (node (ref "C20") (pin "1") (pinfunction "1_1") (pintype "passive"))
      (node (ref "R20") (pin "1") (pinfunction "1_1") (pintype "passive"))
      (node (ref "R35") (pin "2") (pinfunction "2_2") (pintype "passive"))
      (node (ref "R36") (pin "1") (pinfunction "1_1") (pintype "passive"))
      (node (ref "U4") (pin "8") (pinfunction "PC0_8") (pintype "passive"))
    )
    (net (code "16") (name "/GREEN_LED") (class "Default")
      (node (ref "R39") (pin "2") (pinfunction "2_2") (pintype "passive"))
      (node (ref "U4") (pin "25") (pinfunction "PC5_25") (pintype "passive"))
    )
    (net (code "17") (name "/KEY_EMERGENCY") (class "Default")
      (node (ref "C17") (pin "2") (pinfunction "2_2") (pintype "passive"))
      (node (ref "R17") (pin "2") (pinfunction "2_2") (pintype "passive"))
      (node (ref "R33") (pin "1") (pinfunction "1_1") (pintype "passive"))
      (node (ref "U4") (pin "2") (pinfunction "PC13_2") (pintype "passive"))
      (node (ref "U5") (pin "6") (pinfunction "VO_6") (pintype "passive"))
    )
    (net (code "18") (name "/KEY_OPEN") (class "Default")
      (node (ref "C16") (pin "1") (pinfunction "1_1") (pintype "passive"))
      (node (ref "P10") (pin "1") (pinfunction "1_1") (pintype "passive"))
      (node (ref "S1") (pin "1") (pinfunction "COMMON1_1") (pintype "passive"))
      (node (ref "S1") (pin "3") (pinfunction "COMMON2_3") (pintype "passive"))
      (node (ref "U4") (pin "27") (pinfunction "PB1_27") (pintype "passive"))
    )
    (net (code "19") (name "/KEY_SET") (class "Default")
      (node (ref "C21") (pin "1") (pinfunction "1_1") (pintype "passive"))
      (node (ref "S2") (pin "1") (pinfunction "COMMON1_1") (pintype "passive"))
      (node (ref "S2") (pin "3") (pinfunction "COMMON2_3") (pintype "passive"))
      (node (ref "U4") (pin "28") (pinfunction "PB2_28") (pintype "passive"))
    )
    (net (code "20") (name "/LE") (class "Default")
      (node (ref "P11") (pin "5") (pinfunction "5_5") (pintype "passive"))
      (node (ref "R49") (pin "2") (pinfunction "2_2") (pintype "passive"))
    )
    (net (code "21") (name "/LORA AUX") (class "Default")
      (node (ref "J4") (pin "6") (pinfunction "6_6") (pintype "passive"))
      (node (ref "R55") (pin "2") (pinfunction "2_2") (pintype "passive"))
    )
    (net (code "22") (name "/LORA SETA") (class "Default")
      (node (ref "J4") (pin "3") (pinfunction "3_3") (pintype "passive"))
      (node (ref "R52") (pin "2") (pinfunction "2_2") (pintype "passive"))
    )
    (net (code "23") (name "/LORA SETB") (class "Default")
      (node (ref "J4") (pin "7") (pinfunction "7_7") (pintype "passive"))
      (node (ref "R56") (pin "2") (pinfunction "2_2") (pintype "passive"))
    )
    (net (code "24") (name "/LORA_RXD") (class "Default")
      (node (ref "J4") (pin "5") (pinfunction "5_5") (pintype "passive"))
      (node (ref "R53") (pin "2") (pinfunction "2_2") (pintype "passive"))
    )
    (net (code "25") (name "/LORA_TXD") (class "Default")
      (node (ref "J4") (pin "4") (pinfunction "4_4") (pintype "passive"))
      (node (ref "R54") (pin "2") (pinfunction "2_2") (pintype "passive"))
    )
    (net (code "26") (name "/MCU_NB_RXD") (class "Default")
      (node (ref "P2") (pin "5") (pinfunction "5_5") (pintype "passive"))
      (node (ref "U4") (pin "17") (pinfunction "PA3_17") (pintype "passive"))
    )
    (net (code "27") (name "/MCU_NB_TXD") (class "Default")
      (node (ref "P2") (pin "6") (pinfunction "6_6") (pintype "passive"))
      (node (ref "U4") (pin "16") (pinfunction "PA2_16") (pintype "passive"))
    )
    (net (code "28") (name "/NB_DTR") (class "Default")
      (node (ref "U1") (pin "19") (pinfunction "DTR_19") (pintype "passive"))
      (node (ref "U4") (pin "33") (pinfunction "PB12_33") (pintype "passive"))
    )
    (net (code "29") (name "/NB_ON{slash}OFF") (class "Default")
      (node (ref "U1") (pin "7") (pinfunction "PWRKEY_7") (pintype "passive"))
      (node (ref "U4") (pin "40") (pinfunction "PC9_40") (pintype "passive"))
    )
    (net (code "30") (name "/NB_POWER") (class "Default")
      (node (ref "Q1") (pin "1") (pinfunction "G_1") (pintype "passive"))
      (node (ref "R4") (pin "1") (pinfunction "1_1") (pintype "passive"))
      (node (ref "U4") (pin "41") (pinfunction "PA8_41") (pintype "passive"))
    )
    (net (code "31") (name "/NB_PWR") (class "Default")
      (node (ref "Q2") (pin "3") (pinfunction "C_3") (pintype "passive"))
      (node (ref "R1") (pin "1") (pinfunction "1_1") (pintype "passive"))
      (node (ref "U4") (pin "45") (pinfunction "PA12_45") (pintype "passive"))
    )
    (net (code "32") (name "/NB_R") (class "Default")
      (node (ref "P2") (pin "4") (pinfunction "4_4") (pintype "passive"))
      (node (ref "Q4") (pin "2") (pinfunction "E_2") (pintype "passive"))
    )
    (net (code "33") (name "/NB_RXD") (class "Default")
      (node (ref "Q4") (pin "3") (pinfunction "C_3") (pintype "passive"))
      (node (ref "R11") (pin "1") (pinfunction "1_1") (pintype "passive"))
      (node (ref "U1") (pin "17") (pinfunction "RXD_17") (pintype "passive"))
    )
    (net (code "34") (name "/NB_RX_DB") (class "Default")
      (node (ref "P7") (pin "2") (pinfunction "2_2") (pintype "passive"))
      (node (ref "U6") (pin "8") (pinfunction "R2IN_8") (pintype "input"))
    )
    (net (code "35") (name "/NB_Reset") (class "Default")
      (node (ref "U1") (pin "15") (pinfunction "RESERVED_15") (pintype "passive"))
      (node (ref "U4") (pin "34") (pinfunction "PB13_34") (pintype "passive"))
    )
    (net (code "36") (name "/NB_T") (class "Default")
      (node (ref "P2") (pin "3") (pinfunction "3_3") (pintype "passive"))
      (node (ref "Q5") (pin "3") (pinfunction "C_3") (pintype "passive"))
      (node (ref "R12") (pin "2") (pinfunction "2_2") (pintype "passive"))
    )
    (net (code "37") (name "/NB_TXD") (class "Default")
      (node (ref "Q5") (pin "2") (pinfunction "E_2") (pintype "passive"))
      (node (ref "U1") (pin "18") (pinfunction "TXD_18") (pintype "passive"))
    )
    (net (code "38") (name "/NB_TX_DB") (class "Default")
      (node (ref "P7") (pin "1") (pinfunction "1_1") (pintype "passive"))
      (node (ref "U6") (pin "7") (pinfunction "T2OUT_7") (pintype "output"))
    )
    (net (code "39") (name "/NRST") (class "Default")
      (node (ref "C22") (pin "1") (pinfunction "1_1") (pintype "passive"))
      (node (ref "R21") (pin "1") (pinfunction "1_1") (pintype "passive"))
      (node (ref "U4") (pin "7") (pinfunction "NRST_7") (pintype "passive"))
    )
    (net (code "40") (name "/PC_RXD") (class "Default")
      (node (ref "P2") (pin "1") (pinfunction "1_1") (pintype "passive"))
      (node (ref "U6") (pin "9") (pinfunction "R2OUT_9") (pintype "output"))
    )
    (net (code "41") (name "/PC_TXD") (class "Default")
      (node (ref "P2") (pin "2") (pinfunction "2_2") (pintype "passive"))
      (node (ref "U6") (pin "10") (pinfunction "T2IN_10") (pintype "input"))
    )
    (net (code "42") (name "/PE") (class "Default")
      (node (ref "P11") (pin "3") (pinfunction "3_3") (pintype "passive"))
      (node (ref "R48") (pin "2") (pinfunction "2_2") (pintype "passive"))
    )
    (net (code "43") (name "/POWER_DOWN") (class "Default")
      (node (ref "Q6") (pin "3") (pinfunction "C_3") (pintype "passive"))
      (node (ref "R30") (pin "1") (pinfunction "1_1") (pintype "passive"))
      (node (ref "U4") (pin "62") (pinfunction "PB9_62") (pintype "passive"))
    )
    (net (code "44") (name "/READER_BEEP") (class "Default")
      (node (ref "R24") (pin "1") (pinfunction "1_1") (pintype "passive"))
      (node (ref "U4") (pin "10") (pinfunction "PC2_10") (pintype "passive"))
    )
    (net (code "45") (name "/READER_D0") (class "Default")
      (node (ref "R28") (pin "1") (pinfunction "1_1") (pintype "passive"))
      (node (ref "U4") (pin "15") (pinfunction "PA1_15") (pintype "passive"))
    )
    (net (code "46") (name "/READER_D1") (class "Default")
      (node (ref "R42") (pin "1") (pinfunction "1_1") (pintype "passive"))
      (node (ref "U4") (pin "14") (pinfunction "PA0_14") (pintype "passive"))
    )
    (net (code "47") (name "/READER_LED") (class "Default")
      (node (ref "R23") (pin "1") (pinfunction "1_1") (pintype "passive"))
      (node (ref "U4") (pin "11") (pinfunction "PC3_11") (pintype "passive"))
    )
    (net (code "48") (name "/RED_LED") (class "Default")
      (node (ref "R38") (pin "2") (pinfunction "2_2") (pintype "passive"))
      (node (ref "U4") (pin "24") (pinfunction "PC4_24") (pintype "passive"))
    )
    (net (code "49") (name "/RESET") (class "Default")
      (node (ref "M1") (pin "4") (pinfunction "RESET_4") (pintype "passive"))
      (node (ref "U4") (pin "61") (pinfunction "PB8_61") (pintype "passive"))
    )
    (net (code "50") (name "/RS232_RXD") (class "Default")
      (node (ref "P6") (pin "2") (pinfunction "2_2") (pintype "passive"))
      (node (ref "U6") (pin "13") (pinfunction "R1IN_13") (pintype "input"))
    )
    (net (code "51") (name "/RS232_TXD") (class "Default")
      (node (ref "P6") (pin "1") (pinfunction "1_1") (pintype "passive"))
      (node (ref "U6") (pin "14") (pinfunction "T1OUT_14") (pintype "output"))
    )
    (net (code "52") (name "/SMOKE_IN") (class "Default")
      (node (ref "P11") (pin "7") (pinfunction "7_7") (pintype "passive"))
      (node (ref "R50") (pin "2") (pinfunction "2_2") (pintype "passive"))
    )
    (net (code "53") (name "/SPI1_MISO") (class "Default")
      (node (ref "R15") (pin "2") (pinfunction "2_2") (pintype "passive"))
      (node (ref "U3") (pin "2") (pinfunction "DO_2") (pintype "passive"))
      (node (ref "U4") (pin "22") (pinfunction "PA6_22") (pintype "passive"))
    )
    (net (code "54") (name "/SPI1_MOSI") (class "Default")
      (node (ref "U3") (pin "5") (pinfunction "DI_5") (pintype "passive"))
      (node (ref "U4") (pin "23") (pinfunction "PA7_23") (pintype "passive"))
    )
    (net (code "55") (name "/SPI1_NSS") (class "Default")
      (node (ref "U3") (pin "1") (pinfunction "~{CS}_1") (pintype "passive"))
      (node (ref "U4") (pin "20") (pinfunction "PA4_20") (pintype "passive"))
    )
    (net (code "56") (name "/SPI1_SCK") (class "Default")
      (node (ref "U3") (pin "6") (pinfunction "CLK_6") (pintype "passive"))
      (node (ref "U4") (pin "21") (pinfunction "PA5_21") (pintype "passive"))
    )
    (net (code "57") (name "/SPI3_MISO") (class "Default")
      (node (ref "M1") (pin "13") (pinfunction "MISO_13") (pintype "passive"))
      (node (ref "U4") (pin "52") (pinfunction "PC11_52") (pintype "passive"))
    )
    (net (code "58") (name "/SPI3_MOSI") (class "Default")
      (node (ref "M1") (pin "14") (pinfunction "MOSI_14") (pintype "passive"))
      (node (ref "U4") (pin "53") (pinfunction "PC12_53") (pintype "passive"))
    )
    (net (code "59") (name "/SPI3_NSS") (class "Default")
      (node (ref "M1") (pin "15") (pinfunction "NSS_15") (pintype "passive"))
      (node (ref "U4") (pin "50") (pinfunction "PA15_50") (pintype "passive"))
    )
    (net (code "60") (name "/SPI3_SCK") (class "Default")
      (node (ref "M1") (pin "12") (pinfunction "SCK_12") (pintype "passive"))
      (node (ref "U4") (pin "51") (pinfunction "PC10_51") (pintype "passive"))
    )
    (net (code "61") (name "/SWCLK") (class "Default")
      (node (ref "J3") (pin "4") (pinfunction "4_4") (pintype "passive"))
      (node (ref "U4") (pin "49") (pinfunction "PA14_49") (pintype "passive"))
    )
    (net (code "62") (name "/SWDIO") (class "Default")
      (node (ref "J3") (pin "3") (pinfunction "3_3") (pintype "passive"))
      (node (ref "U4") (pin "46") (pinfunction "PA13_46") (pintype "passive"))
    )
    (net (code "63") (name "/WG_BEEP") (class "Default")
      (node (ref "P5") (pin "6") (pinfunction "6_6") (pintype "passive"))
      (node (ref "Q10") (pin "3") (pinfunction "C_3") (pintype "passive"))
    )
    (net (code "64") (name "/WG_D0") (class "Default")
      (node (ref "P5") (pin "3") (pinfunction "3_3") (pintype "passive"))
      (node (ref "R43") (pin "2") (pinfunction "2_2") (pintype "passive"))
    )
    (net (code "65") (name "/WG_D1") (class "Default")
      (node (ref "P5") (pin "4") (pinfunction "4_4") (pintype "passive"))
      (node (ref "R44") (pin "2") (pinfunction "2_2") (pintype "passive"))
    )
    (net (code "66") (name "/WG_LED") (class "Default")
      (node (ref "P5") (pin "5") (pinfunction "5_5") (pintype "passive"))
      (node (ref "Q9") (pin "3") (pinfunction "C_3") (pintype "passive"))
    )
    (net (code "67") (name "/YELLOW_LED") (class "Default")
      (node (ref "R40") (pin "2") (pinfunction "2_2") (pintype "passive"))
      (node (ref "U4") (pin "26") (pinfunction "PB0_26") (pintype "passive"))
    )
    (net (code "68") (name "/sim_clk") (class "Default")
      (node (ref "J2") (pin "1") (pinfunction "1_1") (pintype "passive"))
      (node (ref "U1") (pin "13") (pinfunction "SIM_CLK_13") (pintype "passive"))
    )
    (net (code "69") (name "/sim_io") (class "Default")
      (node (ref "J2") (pin "6") (pinfunction "6_6") (pintype "passive"))
      (node (ref "U1") (pin "11") (pinfunction "SIM_DATA_11") (pintype "passive"))
    )
    (net (code "70") (name "/sim_reset") (class "Default")
      (node (ref "J2") (pin "2") (pinfunction "2_2") (pintype "passive"))
      (node (ref "U1") (pin "12") (pinfunction "SIM_RST_12") (pintype "passive"))
    )
    (net (code "71") (name "/sim_vcc") (class "Default")
      (node (ref "J2") (pin "3") (pinfunction "3_3") (pintype "passive"))
      (node (ref "J2") (pin "5") (pinfunction "5_5") (pintype "passive"))
      (node (ref "U1") (pin "14") (pinfunction "SIM_VDD_14") (pintype "passive"))
    )
    (net (code "72") (name "3V3") (class "Default")
      (node (ref "C15") (pin "1") (pinfunction "1_1") (pintype "passive"))
      (node (ref "C23") (pin "1") (pinfunction "1_1") (pintype "passive"))
      (node (ref "C25") (pin "1") (pinfunction "1_1") (pintype "passive"))
      (node (ref "C26") (pin "2") (pinfunction "2_2") (pintype "passive"))
      (node (ref "C27") (pin "2") (pinfunction "2_2") (pintype "passive"))
      (node (ref "C28") (pin "2") (pinfunction "2_2") (pintype "passive"))
      (node (ref "C29") (pin "2") (pinfunction "2_2") (pintype "passive"))
      (node (ref "C3") (pin "1") (pinfunction "1_1") (pintype "passive"))
      (node (ref "C30") (pin "2") (pinfunction "2_2") (pintype "passive"))
      (node (ref "C31") (pin "2") (pinfunction "2_2") (pintype "passive"))
      (node (ref "C33") (pin "2") (pinfunction "2_2") (pintype "passive"))
      (node (ref "C35") (pin "2") (pinfunction "2_2") (pintype "passive"))
      (node (ref "C4") (pin "2") (pinfunction "2_2") (pintype "passive"))
      (node (ref "C43") (pin "1") (pinfunction "1_1") (pintype "passive"))
      (node (ref "D1") (pin "A") (pinfunction "A_A") (pintype "passive"))
      (node (ref "D13") (pin "A") (pinfunction "A_A") (pintype "passive"))
      (node (ref "D5") (pin "A") (pinfunction "A_A") (pintype "passive"))
      (node (ref "D7") (pin "A") (pinfunction "A_A") (pintype "passive"))
      (node (ref "D8") (pin "A") (pinfunction "A_A") (pintype "passive"))
      (node (ref "D9") (pin "A") (pinfunction "A_A") (pintype "passive"))
      (node (ref "J3") (pin "1") (pinfunction "1_1") (pintype "passive"))
      (node (ref "J4") (pin "2") (pinfunction "2_2") (pintype "passive"))
      (node (ref "M1") (pin "3") (pinfunction "3V3_3") (pintype "passive"))
      (node (ref "Q1") (pin "2") (pinfunction "S_2") (pintype "passive"))
      (node (ref "R1") (pin "2") (pinfunction "2_2") (pintype "passive"))
      (node (ref "R12") (pin "1") (pinfunction "1_1") (pintype "passive"))
      (node (ref "R13") (pin "2") (pinfunction "2_2") (pintype "passive"))
      (node (ref "R15") (pin "1") (pinfunction "1_1") (pintype "passive"))
      (node (ref "R17") (pin "1") (pinfunction "1_1") (pintype "passive"))
      (node (ref "R2") (pin "2") (pinfunction "2_2") (pintype "passive"))
      (node (ref "R21") (pin "2") (pinfunction "2_2") (pintype "passive"))
      (node (ref "R25") (pin "2") (pinfunction "2_2") (pintype "passive"))
      (node (ref "R26") (pin "1") (pinfunction "1_1") (pintype "passive"))
      (node (ref "R27") (pin "1") (pinfunction "1_1") (pintype "passive"))
      (node (ref "R30") (pin "2") (pinfunction "2_2") (pintype "passive"))
      (node (ref "R4") (pin "2") (pinfunction "2_2") (pintype "passive"))
      (node (ref "R41") (pin "2") (pinfunction "2_2") (pintype "passive"))
      (node (ref "U3") (pin "3") (pinfunction "~{WP}_3") (pintype "passive"))
      (node (ref "U3") (pin "7") (pinfunction "~{HOLD}_7") (pintype "passive"))
      (node (ref "U3") (pin "8") (pinfunction "VCC_8") (pintype "passive"))
      (node (ref "U4") (pin "1") (pinfunction "VBAT_1") (pintype "passive"))
      (node (ref "U4") (pin "13") (pinfunction "VDDA/REF+_13") (pintype "passive"))
      (node (ref "U4") (pin "19") (pinfunction "VDD_19") (pintype "passive"))
      (node (ref "U4") (pin "32") (pinfunction "VDD_32") (pintype "passive"))
      (node (ref "U4") (pin "48") (pinfunction "VDD_48") (pintype "passive"))
      (node (ref "U4") (pin "64") (pinfunction "VDD_64") (pintype "passive"))
      (node (ref "U5") (pin "8") (pinfunction "VCC_8") (pintype "passive"))
      (node (ref "U6") (pin "16") (pinfunction "VCC_16") (pintype "power_in"))
    )
    (net (code "73") (name "5V") (class "Default")
      (node (ref "C10") (pin "1") (pinfunction "1_1") (pintype "passive"))
      (node (ref "C11") (pin "1") (pinfunction "1_1") (pintype "passive"))
      (node (ref "D11") (pin "1") (pinfunction "A_1") (pintype "passive"))
      (node (ref "D12") (pin "2") (pinfunction "K_2") (pintype "passive"))
      (node (ref "K2") (pin "4") (pinfunction "4_4") (pintype "passive"))
      (node (ref "L1") (pin "2") (pinfunction "2_2") (pintype "passive"))
      (node (ref "Q8") (pin "2") (pinfunction "E_2") (pintype "passive"))
      (node (ref "R31") (pin "2") (pinfunction "2_2") (pintype "passive"))
      (node (ref "R9") (pin "2") (pinfunction "2_2") (pintype "passive"))
    )
    (net (code "74") (name "GND") (class "Default")
      (node (ref "BT1") (pin "2") (pinfunction "-_2") (pintype "passive"))
      (node (ref "C1") (pin "1") (pinfunction "1_1") (pintype "passive"))
      (node (ref "C10") (pin "2") (pinfunction "2_2") (pintype "passive"))
      (node (ref "C11") (pin "2") (pinfunction "2_2") (pintype "passive"))
      (node (ref "C13") (pin "1") (pinfunction "1_1") (pintype "passive"))
      (node (ref "C15") (pin "2") (pinfunction "2_2") (pintype "passive"))
      (node (ref "C16") (pin "2") (pinfunction "2_2") (pintype "passive"))
      (node (ref "C17") (pin "1") (pinfunction "1_1") (pintype "passive"))
      (node (ref "C18") (pin "1") (pinfunction "1_1") (pintype "passive"))
      (node (ref "C19") (pin "2") (pinfunction "2_2") (pintype "passive"))
      (node (ref "C2") (pin "1") (pinfunction "1_1") (pintype "passive"))
      (node (ref "C20") (pin "2") (pinfunction "2_2") (pintype "passive"))
      (node (ref "C21") (pin "2") (pinfunction "2_2") (pintype "passive"))
      (node (ref "C22") (pin "2") (pinfunction "2_2") (pintype "passive"))
      (node (ref "C23") (pin "2") (pinfunction "2_2") (pintype "passive"))
      (node (ref "C24") (pin "2") (pinfunction "2_2") (pintype "passive"))
      (node (ref "C25") (pin "2") (pinfunction "2_2") (pintype "passive"))
      (node (ref "C26") (pin "1") (pinfunction "1_1") (pintype "passive"))
      (node (ref "C27") (pin "1") (pinfunction "1_1") (pintype "passive"))
      (node (ref "C28") (pin "1") (pinfunction "1_1") (pintype "passive"))
      (node (ref "C29") (pin "1") (pinfunction "1_1") (pintype "passive"))
      (node (ref "C3") (pin "2") (pinfunction "2_2") (pintype "passive"))
      (node (ref "C30") (pin "1") (pinfunction "1_1") (pintype "passive"))
      (node (ref "C31") (pin "1") (pinfunction "1_1") (pintype "passive"))
      (node (ref "C35") (pin "1") (pinfunction "1_1") (pintype "passive"))
      (node (ref "C36") (pin "2") (pinfunction "2_2") (pintype "passive"))
      (node (ref "C37") (pin "2") (pinfunction "2_2") (pintype "passive"))
      (node (ref "C38") (pin "1") (pinfunction "1_1") (pintype "passive"))
      (node (ref "C39") (pin "2") (pinfunction "2_2") (pintype "passive"))
      (node (ref "C4") (pin "1") (pinfunction "1_1") (pintype "passive"))
      (node (ref "C40") (pin "2") (pinfunction "2_2") (pintype "passive"))
      (node (ref "C41") (pin "2") (pinfunction "2_2") (pintype "passive"))
      (node (ref "C42") (pin "2") (pinfunction "2_2") (pintype "passive"))
      (node (ref "C43") (pin "2") (pinfunction "2_2") (pintype "passive"))
      (node (ref "C5") (pin "2") (pinfunction "2_2") (pintype "passive"))
      (node (ref "C6") (pin "1") (pinfunction "1_1") (pintype "passive"))
      (node (ref "C7") (pin "1") (pinfunction "1_1") (pintype "passive"))
      (node (ref "D15") (pin "1") (pinfunction "A_1") (pintype "passive"))
      (node (ref "D2") (pin "1") (pinfunction "A_1") (pintype "passive"))
      (node (ref "D3") (pin "K") (pinfunction "K_K") (pintype "passive"))
      (node (ref "J1") (pin "2") (pinfunction "2_2") (pintype "passive"))
      (node (ref "J1") (pin "3") (pinfunction "3_3") (pintype "passive"))
      (node (ref "J1") (pin "4") (pinfunction "4_4") (pintype "passive"))
      (node (ref "J1") (pin "5") (pinfunction "5_5") (pintype "passive"))
      (node (ref "J2") (pin "4") (pinfunction "4_4") (pintype "passive"))
      (node (ref "J2") (pin "7") (pinfunction "7_7") (pintype "passive"))
      (node (ref "J2") (pin "8") (pinfunction "8_8") (pintype "passive"))
      (node (ref "J3") (pin "2") (pinfunction "2_2") (pintype "passive"))
      (node (ref "J4") (pin "1") (pinfunction "1_1") (pintype "passive"))
      (node (ref "J5") (pin "2") (pinfunction "2_2") (pintype "passive"))
      (node (ref "J5") (pin "3") (pinfunction "3_3") (pintype "passive"))
      (node (ref "J5") (pin "4") (pinfunction "4_4") (pintype "passive"))
      (node (ref "J5") (pin "5") (pinfunction "5_5") (pintype "passive"))
      (node (ref "J6") (pin "2") (pinfunction "2_2") (pintype "passive"))
      (node (ref "J6") (pin "3") (pinfunction "3_3") (pintype "passive"))
      (node (ref "K1") (pin "1") (pinfunction "1_1") (pintype "passive"))
      (node (ref "K1") (pin "2") (pinfunction "2_2") (pintype "passive"))
      (node (ref "K2") (pin "2") (pinfunction "2_2") (pintype "passive"))
      (node (ref "M1") (pin "16") (pinfunction "GND_16") (pintype "passive"))
      (node (ref "M1") (pin "2") (pinfunction "GND_2") (pintype "passive"))
      (node (ref "M1") (pin "9") (pinfunction "GND_9") (pintype "passive"))
      (node (ref "P10") (pin "2") (pinfunction "2_2") (pintype "passive"))
      (node (ref "P11") (pin "10") (pinfunction "10_10") (pintype "passive"))
      (node (ref "P11") (pin "2") (pinfunction "2_2") (pintype "passive"))
      (node (ref "P11") (pin "4") (pinfunction "4_4") (pintype "passive"))
      (node (ref "P11") (pin "6") (pinfunction "6_6") (pintype "passive"))
      (node (ref "P11") (pin "8") (pinfunction "8_8") (pintype "passive"))
      (node (ref "P5") (pin "2") (pinfunction "2_2") (pintype "passive"))
      (node (ref "P6") (pin "3") (pinfunction "3_3") (pintype "passive"))
      (node (ref "P7") (pin "3") (pinfunction "3_3") (pintype "passive"))
      (node (ref "P8") (pin "1") (pinfunction "1_1") (pintype "passive"))
      (node (ref "Q10") (pin "2") (pinfunction "E_2") (pintype "passive"))
      (node (ref "Q11") (pin "2") (pinfunction "E_2") (pintype "passive"))
      (node (ref "Q12") (pin "2") (pinfunction "E_2") (pintype "passive"))
      (node (ref "Q2") (pin "2") (pinfunction "E_2") (pintype "passive"))
      (node (ref "Q3") (pin "2") (pinfunction "E_2") (pintype "passive"))
      (node (ref "Q6") (pin "2") (pinfunction "E_2") (pintype "passive"))
      (node (ref "Q7") (pin "2") (pinfunction "E_2") (pintype "passive"))
      (node (ref "Q9") (pin "2") (pinfunction "E_2") (pintype "passive"))
      (node (ref "R29") (pin "2") (pinfunction "2_2") (pintype "passive"))
      (node (ref "R34") (pin "1") (pinfunction "1_1") (pintype "passive"))
      (node (ref "R35") (pin "1") (pinfunction "1_1") (pintype "passive"))
      (node (ref "R45") (pin "2") (pinfunction "2_2") (pintype "passive"))
      (node (ref "R46") (pin "2") (pinfunction "2_2") (pintype "passive"))
      (node (ref "R5") (pin "2") (pinfunction "2_2") (pintype "passive"))
      (node (ref "R8") (pin "2") (pinfunction "2_2") (pintype "passive"))
      (node (ref "S1") (pin "2") (pinfunction "NO1_2") (pintype "passive"))
      (node (ref "S1") (pin "4") (pinfunction "NO2_4") (pintype "passive"))
      (node (ref "S2") (pin "2") (pinfunction "NO1_2") (pintype "passive"))
      (node (ref "S2") (pin "4") (pinfunction "NO2_4") (pintype "passive"))
      (node (ref "U1") (pin "1") (pinfunction "AGND_1") (pintype "passive"))
      (node (ref "U1") (pin "10") (pinfunction "SIM_GND_10") (pintype "passive"))
      (node (ref "U1") (pin "27") (pinfunction "GND_27") (pintype "passive"))
      (node (ref "U1") (pin "34") (pinfunction "GND_34") (pintype "passive"))
      (node (ref "U1") (pin "36") (pinfunction "GND_36") (pintype "passive"))
      (node (ref "U1") (pin "37") (pinfunction "GND_37") (pintype "passive"))
      (node (ref "U1") (pin "40") (pinfunction "GND_40") (pintype "passive"))
      (node (ref "U1") (pin "41") (pinfunction "GND_41") (pintype "passive"))
      (node (ref "U2") (pin "4") (pinfunction "GND_4") (pintype "passive"))
      (node (ref "U3") (pin "4") (pinfunction "GND_4") (pintype "passive"))
      (node (ref "U4") (pin "12") (pinfunction "VSSA/VREF-_12") (pintype "passive"))
      (node (ref "U4") (pin "18") (pinfunction "VSS_18") (pintype "passive"))
      (node (ref "U4") (pin "31") (pinfunction "VSS_31") (pintype "passive"))
      (node (ref "U4") (pin "47") (pinfunction "VSS_47") (pintype "passive"))
      (node (ref "U4") (pin "63") (pinfunction "VSS_63") (pintype "passive"))
      (node (ref "U5") (pin "3") (pinfunction "K_3") (pintype "passive"))
      (node (ref "U5") (pin "5") (pinfunction "GND_5") (pintype "passive"))
      (node (ref "U6") (pin "15") (pinfunction "GND_15") (pintype "power_in"))
      (node (ref "U7") (pin "3") (pinfunction "PGND_3") (pintype "passive"))
      (node (ref "U7") (pin "9") (pinfunction "GND_9") (pintype "passive"))
      (node (ref "VR1") (pin "1") (pinfunction "GND_1") (pintype "passive"))
      (node (ref "W1") (pin "1") (pinfunction "C1_1") (pintype "passive"))
      (node (ref "W2") (pin "1") (pinfunction "C1_1") (pintype "passive"))
    )
    (net (code "75") (name "Net-(BT1-+)") (class "Default")
      (node (ref "BT1") (pin "1") (pinfunction "+_1") (pintype "passive"))
      (node (ref "D6") (pin "1") (pinfunction "A_1") (pintype "passive"))
      (node (ref "R19") (pin "2") (pinfunction "2_2") (pintype "passive"))
    )
    (net (code "76") (name "Net-(C9-Pad1)") (class "Default")
      (node (ref "C9") (pin "1") (pinfunction "1_1") (pintype "passive"))
      (node (ref "R5") (pin "1") (pinfunction "1_1") (pintype "passive"))
    )
    (net (code "77") (name "Net-(D1-PadK)") (class "Default")
      (node (ref "D1") (pin "K") (pinfunction "K_K") (pintype "passive"))
      (node (ref "R29") (pin "1") (pinfunction "1_1") (pintype "passive"))
    )
    (net (code "78") (name "Net-(D2-K)") (class "Default")
      (node (ref "C8") (pin "1") (pinfunction "1_1") (pintype "passive"))
      (node (ref "D2") (pin "2") (pinfunction "K_2") (pintype "passive"))
      (node (ref "L1") (pin "1") (pinfunction "1_1") (pintype "passive"))
      (node (ref "U2") (pin "3") (pinfunction "SW_3") (pintype "passive"))
    )
    (net (code "79") (name "Net-(D3-PadA)") (class "Default")
      (node (ref "D3") (pin "A") (pinfunction "A_A") (pintype "passive"))
      (node (ref "R32") (pin "2") (pinfunction "2_2") (pintype "passive"))
    )
    (net (code "80") (name "Net-(D4-K)") (class "Default")
      (node (ref "D4") (pin "2") (pinfunction "K_2") (pintype "passive"))
      (node (ref "R19") (pin "1") (pinfunction "1_1") (pintype "passive"))
    )
    (net (code "81") (name "Net-(D5-PadK)") (class "Default")
      (node (ref "D5") (pin "K") (pinfunction "K_K") (pintype "passive"))
      (node (ref "R33") (pin "2") (pinfunction "2_2") (pintype "passive"))
    )
    (net (code "82") (name "Net-(D7-PadK)") (class "Default")
      (node (ref "D7") (pin "K") (pinfunction "K_K") (pintype "passive"))
      (node (ref "R38") (pin "1") (pinfunction "1_1") (pintype "passive"))
    )
    (net (code "83") (name "Net-(D8-PadK)") (class "Default")
      (node (ref "D8") (pin "K") (pinfunction "K_K") (pintype "passive"))
      (node (ref "R39") (pin "1") (pinfunction "1_1") (pintype "passive"))
    )
    (net (code "84") (name "Net-(D9-PadK)") (class "Default")
      (node (ref "D9") (pin "K") (pinfunction "K_K") (pintype "passive"))
      (node (ref "R40") (pin "1") (pinfunction "1_1") (pintype "passive"))
    )
    (net (code "85") (name "Net-(D10-A)") (class "Default")
      (node (ref "D10") (pin "1") (pinfunction "A_1") (pintype "passive"))
      (node (ref "P1") (pin "1") (pinfunction "1_1") (pintype "passive"))
    )
    (net (code "86") (name "Net-(D11-K)") (class "Default")
      (node (ref "D11") (pin "2") (pinfunction "K_2") (pintype "passive"))
      (node (ref "D4") (pin "1") (pinfunction "A_1") (pintype "passive"))
      (node (ref "D6") (pin "2") (pinfunction "K_2") (pintype "passive"))
      (node (ref "R22") (pin "1") (pinfunction "1_1") (pintype "passive"))
      (node (ref "R6") (pin "1") (pinfunction "1_1") (pintype "passive"))
    )
    (net (code "87") (name "Net-(D12-A)") (class "Default")
      (node (ref "D12") (pin "1") (pinfunction "A_1") (pintype "passive"))
      (node (ref "K2") (pin "1") (pinfunction "1_1") (pintype "passive"))
      (node (ref "Q7") (pin "3") (pinfunction "C_3") (pintype "passive"))
    )
    (net (code "88") (name "Net-(D13-PadK)") (class "Default")
      (node (ref "D13") (pin "K") (pinfunction "K_K") (pintype "passive"))
      (node (ref "R36") (pin "2") (pinfunction "2_2") (pintype "passive"))
    )
    (net (code "89") (name "Net-(D14-PadK)") (class "Default")
      (node (ref "D14") (pin "K") (pinfunction "K_K") (pintype "passive"))
      (node (ref "R34") (pin "2") (pinfunction "2_2") (pintype "passive"))
    )
    (net (code "90") (name "Net-(D15-K)") (class "Default")
      (node (ref "D15") (pin "2") (pinfunction "K_2") (pintype "passive"))
      (node (ref "K1") (pin "4") (pinfunction "4_4") (pintype "passive"))
      (node (ref "Q8") (pin "3") (pinfunction "C_3") (pintype "passive"))
    )
    (net (code "91") (name "Net-(K1-Pad3)") (class "Default")
      (node (ref "K1") (pin "3") (pinfunction "3_3") (pintype "passive"))
      (node (ref "P4") (pin "2") (pinfunction "2_2") (pintype "passive"))
    )
    (net (code "92") (name "Net-(K2-Pad3)") (class "Default")
      (node (ref "K2") (pin "3") (pinfunction "3_3") (pintype "passive"))
      (node (ref "P9") (pin "2") (pinfunction "2_2") (pintype "passive"))
    )
    (net (code "93") (name "Net-(M1-ANT)") (class "Default")
      (node (ref "J5") (pin "1") (pinfunction "1_1") (pintype "passive"))
      (node (ref "J6") (pin "1") (pinfunction "1_1") (pintype "passive"))
      (node (ref "M1") (pin "1") (pinfunction "ANT_1") (pintype "passive"))
    )
    (net (code "94") (name "Net-(P1-Pad2)") (class "Default")
      (node (ref "P1") (pin "2") (pinfunction "2_2") (pintype "passive"))
      (node (ref "P8") (pin "2") (pinfunction "2_2") (pintype "passive"))
    )
    (net (code "95") (name "Net-(P3-Pad2)") (class "Default")
      (node (ref "P3") (pin "2") (pinfunction "2_2") (pintype "passive"))
      (node (ref "R18") (pin "2") (pinfunction "2_2") (pintype "passive"))
    )
    (net (code "96") (name "Net-(Q1-D)") (class "Default")
      (node (ref "Q1") (pin "3") (pinfunction "D_3") (pintype "passive"))
      (node (ref "U1") (pin "42") (pinfunction "VBAT_42") (pintype "passive"))
      (node (ref "U1") (pin "43") (pinfunction "VBAT_43") (pintype "passive"))
    )
    (net (code "97") (name "Net-(Q2-B)") (class "Default")
      (node (ref "Q2") (pin "1") (pinfunction "B_1") (pintype "passive"))
      (node (ref "Q3") (pin "3") (pinfunction "C_3") (pintype "passive"))
      (node (ref "R2") (pin "1") (pinfunction "1_1") (pintype "passive"))
    )
    (net (code "98") (name "Net-(Q3-B)") (class "Default")
      (node (ref "Q3") (pin "1") (pinfunction "B_1") (pintype "passive"))
      (node (ref "R7") (pin "1") (pinfunction "1_1") (pintype "passive"))
    )
    (net (code "99") (name "Net-(Q4-B)") (class "Default")
      (node (ref "C12") (pin "1") (pinfunction "1_1") (pintype "passive"))
      (node (ref "Q4") (pin "1") (pinfunction "B_1") (pintype "passive"))
      (node (ref "R10") (pin "1") (pinfunction "1_1") (pintype "passive"))
    )
    (net (code "100") (name "Net-(Q5-B)") (class "Default")
      (node (ref "C14") (pin "2") (pinfunction "2_2") (pintype "passive"))
      (node (ref "Q5") (pin "1") (pinfunction "B_1") (pintype "passive"))
      (node (ref "R14") (pin "2") (pinfunction "2_2") (pintype "passive"))
    )
    (net (code "101") (name "Net-(Q6-B)") (class "Default")
      (node (ref "Q6") (pin "1") (pinfunction "B_1") (pintype "passive"))
      (node (ref "R31") (pin "1") (pinfunction "1_1") (pintype "passive"))
    )
    (net (code "102") (name "Net-(Q7-B)") (class "Default")
      (node (ref "Q7") (pin "1") (pinfunction "B_1") (pintype "passive"))
      (node (ref "R37") (pin "2") (pinfunction "2_2") (pintype "passive"))
    )
    (net (code "103") (name "Net-(Q8-B)") (class "Default")
      (node (ref "Q8") (pin "1") (pinfunction "B_1") (pintype "passive"))
      (node (ref "R20") (pin "2") (pinfunction "2_2") (pintype "passive"))
    )
    (net (code "104") (name "Net-(Q9-B)") (class "Default")
      (node (ref "Q9") (pin "1") (pinfunction "B_1") (pintype "passive"))
      (node (ref "R23") (pin "2") (pinfunction "2_2") (pintype "passive"))
    )
    (net (code "105") (name "Net-(Q10-B)") (class "Default")
      (node (ref "Q10") (pin "1") (pinfunction "B_1") (pintype "passive"))
      (node (ref "R24") (pin "2") (pinfunction "2_2") (pintype "passive"))
    )
    (net (code "106") (name "Net-(Q11-B)") (class "Default")
      (node (ref "Q11") (pin "1") (pinfunction "B_1") (pintype "passive"))
      (node (ref "R43") (pin "1") (pinfunction "1_1") (pintype "passive"))
      (node (ref "R45") (pin "1") (pinfunction "1_1") (pintype "passive"))
    )
    (net (code "107") (name "Net-(Q11-C)") (class "Default")
      (node (ref "Q11") (pin "3") (pinfunction "C_3") (pintype "passive"))
      (node (ref "R26") (pin "2") (pinfunction "2_2") (pintype "passive"))
      (node (ref "R28") (pin "2") (pinfunction "2_2") (pintype "passive"))
    )
    (net (code "108") (name "Net-(Q12-B)") (class "Default")
      (node (ref "Q12") (pin "1") (pinfunction "B_1") (pintype "passive"))
      (node (ref "R44") (pin "1") (pinfunction "1_1") (pintype "passive"))
      (node (ref "R46") (pin "1") (pinfunction "1_1") (pintype "passive"))
    )
    (net (code "109") (name "Net-(Q12-C)") (class "Default")
      (node (ref "Q12") (pin "3") (pinfunction "C_3") (pintype "passive"))
      (node (ref "R27") (pin "2") (pinfunction "2_2") (pintype "passive"))
      (node (ref "R42") (pin "2") (pinfunction "2_2") (pintype "passive"))
    )
    (net (code "110") (name "Net-(U1-NETLIGHT)") (class "Default")
      (node (ref "R32") (pin "1") (pinfunction "1_1") (pintype "passive"))
      (node (ref "U1") (pin "16") (pinfunction "NETLIGHT_16") (pintype "passive"))
    )
    (net (code "111") (name "Net-(U1-RF_ANT)") (class "Default")
      (node (ref "J1") (pin "1") (pinfunction "1_1") (pintype "passive"))
      (node (ref "U1") (pin "35") (pinfunction "RF_ANT_35") (pintype "passive"))
    )
    (net (code "112") (name "Net-(U2-BS)") (class "Default")
      (node (ref "C8") (pin "2") (pinfunction "2_2") (pintype "passive"))
      (node (ref "U2") (pin "1") (pinfunction "BS_1") (pintype "passive"))
    )
    (net (code "113") (name "Net-(U2-COMP)") (class "Default")
      (node (ref "C9") (pin "2") (pinfunction "2_2") (pintype "passive"))
      (node (ref "U2") (pin "6") (pinfunction "COMP_6") (pintype "passive"))
    )
    (net (code "114") (name "Net-(U2-EN)") (class "Default")
      (node (ref "R3") (pin "2") (pinfunction "2_2") (pintype "passive"))
      (node (ref "U2") (pin "7") (pinfunction "EN_7") (pintype "passive"))
    )
    (net (code "115") (name "Net-(U2-FB)") (class "Default")
      (node (ref "R8") (pin "1") (pinfunction "1_1") (pintype "passive"))
      (node (ref "R9") (pin "1") (pinfunction "1_1") (pintype "passive"))
      (node (ref "U2") (pin "5") (pinfunction "FB_5") (pintype "passive"))
    )
    (net (code "116") (name "Net-(U2-SS)") (class "Default")
      (node (ref "C7") (pin "2") (pinfunction "2_2") (pintype "passive"))
      (node (ref "U2") (pin "8") (pinfunction "SS_8") (pintype "passive"))
    )
    (net (code "117") (name "Net-(U4-OSC_IN)") (class "Default")
      (node (ref "C18") (pin "2") (pinfunction "2_2") (pintype "passive"))
      (node (ref "U4") (pin "5") (pinfunction "OSC_IN_5") (pintype "passive"))
      (node (ref "Y1") (pin "1") (pinfunction "OSC1_1") (pintype "passive"))
    )
    (net (code "118") (name "Net-(U4-OSC_OUT)") (class "Default")
      (node (ref "C19") (pin "1") (pinfunction "1_1") (pintype "passive"))
      (node (ref "U4") (pin "6") (pinfunction "OSC_OUT_6") (pintype "passive"))
      (node (ref "Y1") (pin "2") (pinfunction "OSC2_2") (pintype "passive"))
    )
    (net (code "119") (name "Net-(U4-PB14)") (class "Default")
      (node (ref "R47") (pin "1") (pinfunction "1_1") (pintype "passive"))
      (node (ref "R56") (pin "1") (pinfunction "1_1") (pintype "passive"))
      (node (ref "U4") (pin "35") (pinfunction "PB14_35") (pintype "passive"))
    )
    (net (code "120") (name "Net-(U4-PB15)") (class "Default")
      (node (ref "R48") (pin "1") (pinfunction "1_1") (pintype "passive"))
      (node (ref "R55") (pin "1") (pinfunction "1_1") (pintype "passive"))
      (node (ref "U4") (pin "36") (pinfunction "PB15_36") (pintype "passive"))
    )
    (net (code "121") (name "Net-(U4-PC6)") (class "Default")
      (node (ref "R49") (pin "1") (pinfunction "1_1") (pintype "passive"))
      (node (ref "R54") (pin "1") (pinfunction "1_1") (pintype "passive"))
      (node (ref "U4") (pin "37") (pinfunction "PC6_37") (pintype "passive"))
    )
    (net (code "122") (name "Net-(U4-PC7)") (class "Default")
      (node (ref "R50") (pin "1") (pinfunction "1_1") (pintype "passive"))
      (node (ref "R53") (pin "1") (pinfunction "1_1") (pintype "passive"))
      (node (ref "U4") (pin "38") (pinfunction "PC7_38") (pintype "passive"))
    )
    (net (code "123") (name "Net-(U4-PC8)") (class "Default")
      (node (ref "R51") (pin "1") (pinfunction "1_1") (pintype "passive"))
      (node (ref "R52") (pin "1") (pinfunction "1_1") (pintype "passive"))
      (node (ref "U4") (pin "39") (pinfunction "PC8_39") (pintype "passive"))
    )
    (net (code "124") (name "Net-(U4-PC14)") (class "Default")
      (node (ref "C38") (pin "2") (pinfunction "2_2") (pintype "passive"))
      (node (ref "U4") (pin "3") (pinfunction "PC14_3") (pintype "passive"))
      (node (ref "Y2") (pin "2") (pinfunction "OSC2_2") (pintype "passive"))
    )
    (net (code "125") (name "Net-(U4-PC15)") (class "Default")
      (node (ref "C37") (pin "1") (pinfunction "1_1") (pintype "passive"))
      (node (ref "U4") (pin "4") (pinfunction "PC15_4") (pintype "passive"))
      (node (ref "Y2") (pin "1") (pinfunction "OSC1_1") (pintype "passive"))
    )
    (net (code "126") (name "Net-(U4-VCAP_1)") (class "Default")
      (node (ref "C24") (pin "1") (pinfunction "1_1") (pintype "passive"))
      (node (ref "U4") (pin "30") (pinfunction "VCAP_1_30") (pintype "passive"))
    )
    (net (code "127") (name "Net-(U5-A)") (class "Default")
      (node (ref "R18") (pin "1") (pinfunction "1_1") (pintype "passive"))
      (node (ref "U5") (pin "2") (pinfunction "A_2") (pintype "passive"))
    )
    (net (code "128") (name "Net-(U6-C1+)") (class "Default")
      (node (ref "C32") (pin "2") (pinfunction "2_2") (pintype "passive"))
      (node (ref "U6") (pin "1") (pinfunction "C1+_1") (pintype "passive"))
    )
    (net (code "129") (name "Net-(U6-C1-)") (class "Default")
      (node (ref "C32") (pin "1") (pinfunction "1_1") (pintype "passive"))
      (node (ref "U6") (pin "3") (pinfunction "C1-_3") (pintype "passive"))
    )
    (net (code "130") (name "Net-(U6-C2+)") (class "Default")
      (node (ref "C34") (pin "1") (pinfunction "1_1") (pintype "passive"))
      (node (ref "U6") (pin "4") (pinfunction "C2+_4") (pintype "passive"))
    )
    (net (code "131") (name "Net-(U6-C2-)") (class "Default")
      (node (ref "C34") (pin "2") (pinfunction "2_2") (pintype "passive"))
      (node (ref "U6") (pin "5") (pinfunction "C2-_5") (pintype "passive"))
    )
    (net (code "132") (name "Net-(U6-VDD)") (class "Default")
      (node (ref "C33") (pin "1") (pinfunction "1_1") (pintype "passive"))
      (node (ref "U6") (pin "2") (pinfunction "VDD_2") (pintype "power_in"))
    )
    (net (code "133") (name "Net-(U6-VEE)") (class "Default")
      (node (ref "C36") (pin "1") (pinfunction "1_1") (pintype "passive"))
      (node (ref "U6") (pin "6") (pinfunction "VEE_6") (pintype "power_in"))
    )
    (net (code "134") (name "Net-(U7-EN)") (class "Default")
      (node (ref "C41") (pin "1") (pinfunction "1_1") (pintype "passive"))
      (node (ref "R16") (pin "1") (pinfunction "1_1") (pintype "passive"))
      (node (ref "U7") (pin "6") (pinfunction "EN_6") (pintype "passive"))
      (node (ref "U7") (pin "7") (pinfunction "PS/SYNC_7") (pintype "passive"))
      (node (ref "U7") (pin "8") (pinfunction "VINA_8") (pintype "passive"))
    )
    (net (code "135") (name "Net-(U7-FB)") (class "Default")
      (node (ref "C39") (pin "1") (pinfunction "1_1") (pintype "passive"))
      (node (ref "C40") (pin "1") (pinfunction "1_1") (pintype "passive"))
      (node (ref "R13") (pin "1") (pinfunction "1_1") (pintype "passive"))
      (node (ref "U7") (pin "1") (pinfunction "VOUT_1") (pintype "passive"))
      (node (ref "U7") (pin "10") (pinfunction "FB_10") (pintype "passive"))
    )
    (net (code "136") (name "Net-(U7-L1)") (class "Default")
      (node (ref "L2") (pin "1") (pinfunction "1_1") (pintype "passive"))
      (node (ref "U7") (pin "4") (pinfunction "L1_4") (pintype "passive"))
    )
    (net (code "137") (name "Net-(U7-L2)") (class "Default")
      (node (ref "L2") (pin "2") (pinfunction "2_2") (pintype "passive"))
      (node (ref "U7") (pin "2") (pinfunction "L2_2") (pintype "passive"))
    )
    (net (code "138") (name "Net-(U7-VIN)") (class "Default")
      (node (ref "C5") (pin "1") (pinfunction "1_1") (pintype "passive"))
      (node (ref "R16") (pin "2") (pinfunction "2_2") (pintype "passive"))
      (node (ref "R6") (pin "2") (pinfunction "2_2") (pintype "passive"))
      (node (ref "U7") (pin "5") (pinfunction "VIN_5") (pintype "passive"))
    )
    (net (code "139") (name "Net-(VR1-Vin)") (class "Default")
      (node (ref "C2") (pin "2") (pinfunction "2_2") (pintype "passive"))
      (node (ref "R22") (pin "2") (pinfunction "2_2") (pintype "passive"))
      (node (ref "VR1") (pin "3") (pinfunction "Vin_3") (pintype "passive"))
    )
    (net (code "140") (name "Net-(VR1-Vout)") (class "Default")
      (node (ref "C6") (pin "2") (pinfunction "2_2") (pintype "passive"))
      (node (ref "R25") (pin "1") (pinfunction "1_1") (pintype "passive"))
      (node (ref "VR1") (pin "2") (pinfunction "Vout_2") (pintype "passive"))
    )
    (net (code "141") (name "Net-(W1-C2)") (class "Default")
      (node (ref "P5") (pin "7") (pinfunction "7_7") (pintype "passive"))
      (node (ref "W1") (pin "2") (pinfunction "C2_2") (pintype "passive"))
    )
    (net (code "142") (name "VDD_EXT") (class "Default")
      (node (ref "C12") (pin "2") (pinfunction "2_2") (pintype "passive"))
      (node (ref "C13") (pin "2") (pinfunction "2_2") (pintype "passive"))
      (node (ref "C14") (pin "1") (pinfunction "1_1") (pintype "passive"))
      (node (ref "R10") (pin "2") (pinfunction "2_2") (pintype "passive"))
      (node (ref "R11") (pin "2") (pinfunction "2_2") (pintype "passive"))
      (node (ref "R14") (pin "1") (pinfunction "1_1") (pintype "passive"))
      (node (ref "R7") (pin "2") (pinfunction "2_2") (pintype "passive"))
      (node (ref "U1") (pin "24") (pinfunction "VDD_EXT_24") (pintype "passive"))
    )
    (net (code "143") (name "unconnected-(P8-Pad3)") (class "Default")
      (node (ref "P8") (pin "3") (pinfunction "3_3") (pintype "passive"))
    )
    (net (code "144") (name "unconnected-(U1-ADC0-Pad9)") (class "Default")
      (node (ref "U1") (pin "9") (pinfunction "ADC0_9") (pintype "passive"))
    )
    (net (code "145") (name "unconnected-(U1-AVDD-Pad8)") (class "Default")
      (node (ref "U1") (pin "8") (pinfunction "AVDD_8") (pintype "passive"))
    )
    (net (code "146") (name "unconnected-(U1-BT_ANT-Pad26)") (class "Default")
      (node (ref "U1") (pin "26") (pinfunction "BT_ANT_26") (pintype "passive"))
    )
    (net (code "147") (name "unconnected-(U1-CTS-Pad22)") (class "Default")
      (node (ref "U1") (pin "22") (pinfunction "CTS_22") (pintype "passive"))
    )
    (net (code "148") (name "unconnected-(U1-DBG_RXD-Pad38)") (class "Default")
      (node (ref "U1") (pin "38") (pinfunction "DBG_RXD_38") (pintype "passive"))
    )
    (net (code "149") (name "unconnected-(U1-DBG_TXD-Pad39)") (class "Default")
      (node (ref "U1") (pin "39") (pinfunction "DBG_TXD_39") (pintype "passive"))
    )
    (net (code "150") (name "unconnected-(U1-DCD-Pad21)") (class "Default")
      (node (ref "U1") (pin "21") (pinfunction "DCD_21") (pintype "passive"))
    )
    (net (code "151") (name "unconnected-(U1-MICN-Pad4)") (class "Default")
      (node (ref "U1") (pin "4") (pinfunction "MICN_4") (pintype "passive"))
    )
    (net (code "152") (name "unconnected-(U1-MICP-Pad3)") (class "Default")
      (node (ref "U1") (pin "3") (pinfunction "MICP_3") (pintype "passive"))
    )
    (net (code "153") (name "unconnected-(U1-PCM_CLK-Pad30)") (class "Default")
      (node (ref "U1") (pin "30") (pinfunction "PCM_CLK_30") (pintype "passive"))
    )
    (net (code "154") (name "unconnected-(U1-PCM_IN-Pad32)") (class "Default")
      (node (ref "U1") (pin "32") (pinfunction "PCM_IN_32") (pintype "passive"))
    )
    (net (code "155") (name "unconnected-(U1-PCM_OUT-Pad33)") (class "Default")
      (node (ref "U1") (pin "33") (pinfunction "PCM_OUT_33") (pintype "passive"))
    )
    (net (code "156") (name "unconnected-(U1-PCM_SYNC-Pad31)") (class "Default")
      (node (ref "U1") (pin "31") (pinfunction "PCM_SYNC_31") (pintype "passive"))
    )
    (net (code "157") (name "unconnected-(U1-RFTXMON-Pad25)") (class "Default")
      (node (ref "U1") (pin "25") (pinfunction "RFTXMON_25") (pintype "passive"))
    )
    (net (code "158") (name "unconnected-(U1-RI-Pad20)") (class "Default")
      (node (ref "U1") (pin "20") (pinfunction "RI_20") (pintype "passive"))
    )
    (net (code "159") (name "unconnected-(U1-RTS-Pad23)") (class "Default")
      (node (ref "U1") (pin "23") (pinfunction "RTS_23") (pintype "passive"))
    )
    (net (code "160") (name "unconnected-(U1-RXD_AUX-Pad28)") (class "Default")
      (node (ref "U1") (pin "28") (pinfunction "RXD_AUX_28") (pintype "passive"))
    )
    (net (code "161") (name "unconnected-(U1-SPK1N-Pad6)") (class "Default")
      (node (ref "U1") (pin "6") (pinfunction "SPK1N_6") (pintype "passive"))
    )
    (net (code "162") (name "unconnected-(U1-SPK1P-Pad5)") (class "Default")
      (node (ref "U1") (pin "5") (pinfunction "SPK1P_5") (pintype "passive"))
    )
    (net (code "163") (name "unconnected-(U1-SPK2P-Pad2)") (class "Default")
      (node (ref "U1") (pin "2") (pinfunction "SPK2P_2") (pintype "passive"))
    )
    (net (code "164") (name "unconnected-(U1-TXD_AUX-Pad29)") (class "Default")
      (node (ref "U1") (pin "29") (pinfunction "TXD_AUX_29") (pintype "passive"))
    )
    (net (code "165") (name "unconnected-(U1-VRTC-Pad44)") (class "Default")
      (node (ref "U1") (pin "44") (pinfunction "VRTC_44") (pintype "passive"))
    )
    (net (code "166") (name "unconnected-(U4-PB10-Pad29)") (class "Default")
      (node (ref "U4") (pin "29") (pinfunction "PB10_29") (pintype "passive"))
    )
    (net (code "167") (name "unconnected-(U4-PC1-Pad9)") (class "Default")
      (node (ref "U4") (pin "9") (pinfunction "PC1_9") (pintype "passive"))
    )
    (net (code "168") (name "unconnected-(U5-NC-Pad1)") (class "Default")
      (node (ref "U5") (pin "1") (pinfunction "NC_1") (pintype "passive"))
    )
    (net (code "169") (name "unconnected-(U5-NC-Pad4)") (class "Default")
      (node (ref "U5") (pin "4") (pinfunction "NC_4") (pintype "passive"))
    )
    (net (code "170") (name "unconnected-(U5-VE-Pad7)") (class "Default")
      (node (ref "U5") (pin "7") (pinfunction "VE_7") (pintype "passive"))
    )
  )
)
